# Roland_memfram.net
KiCad netlist of a schematic drawn in EAGLE
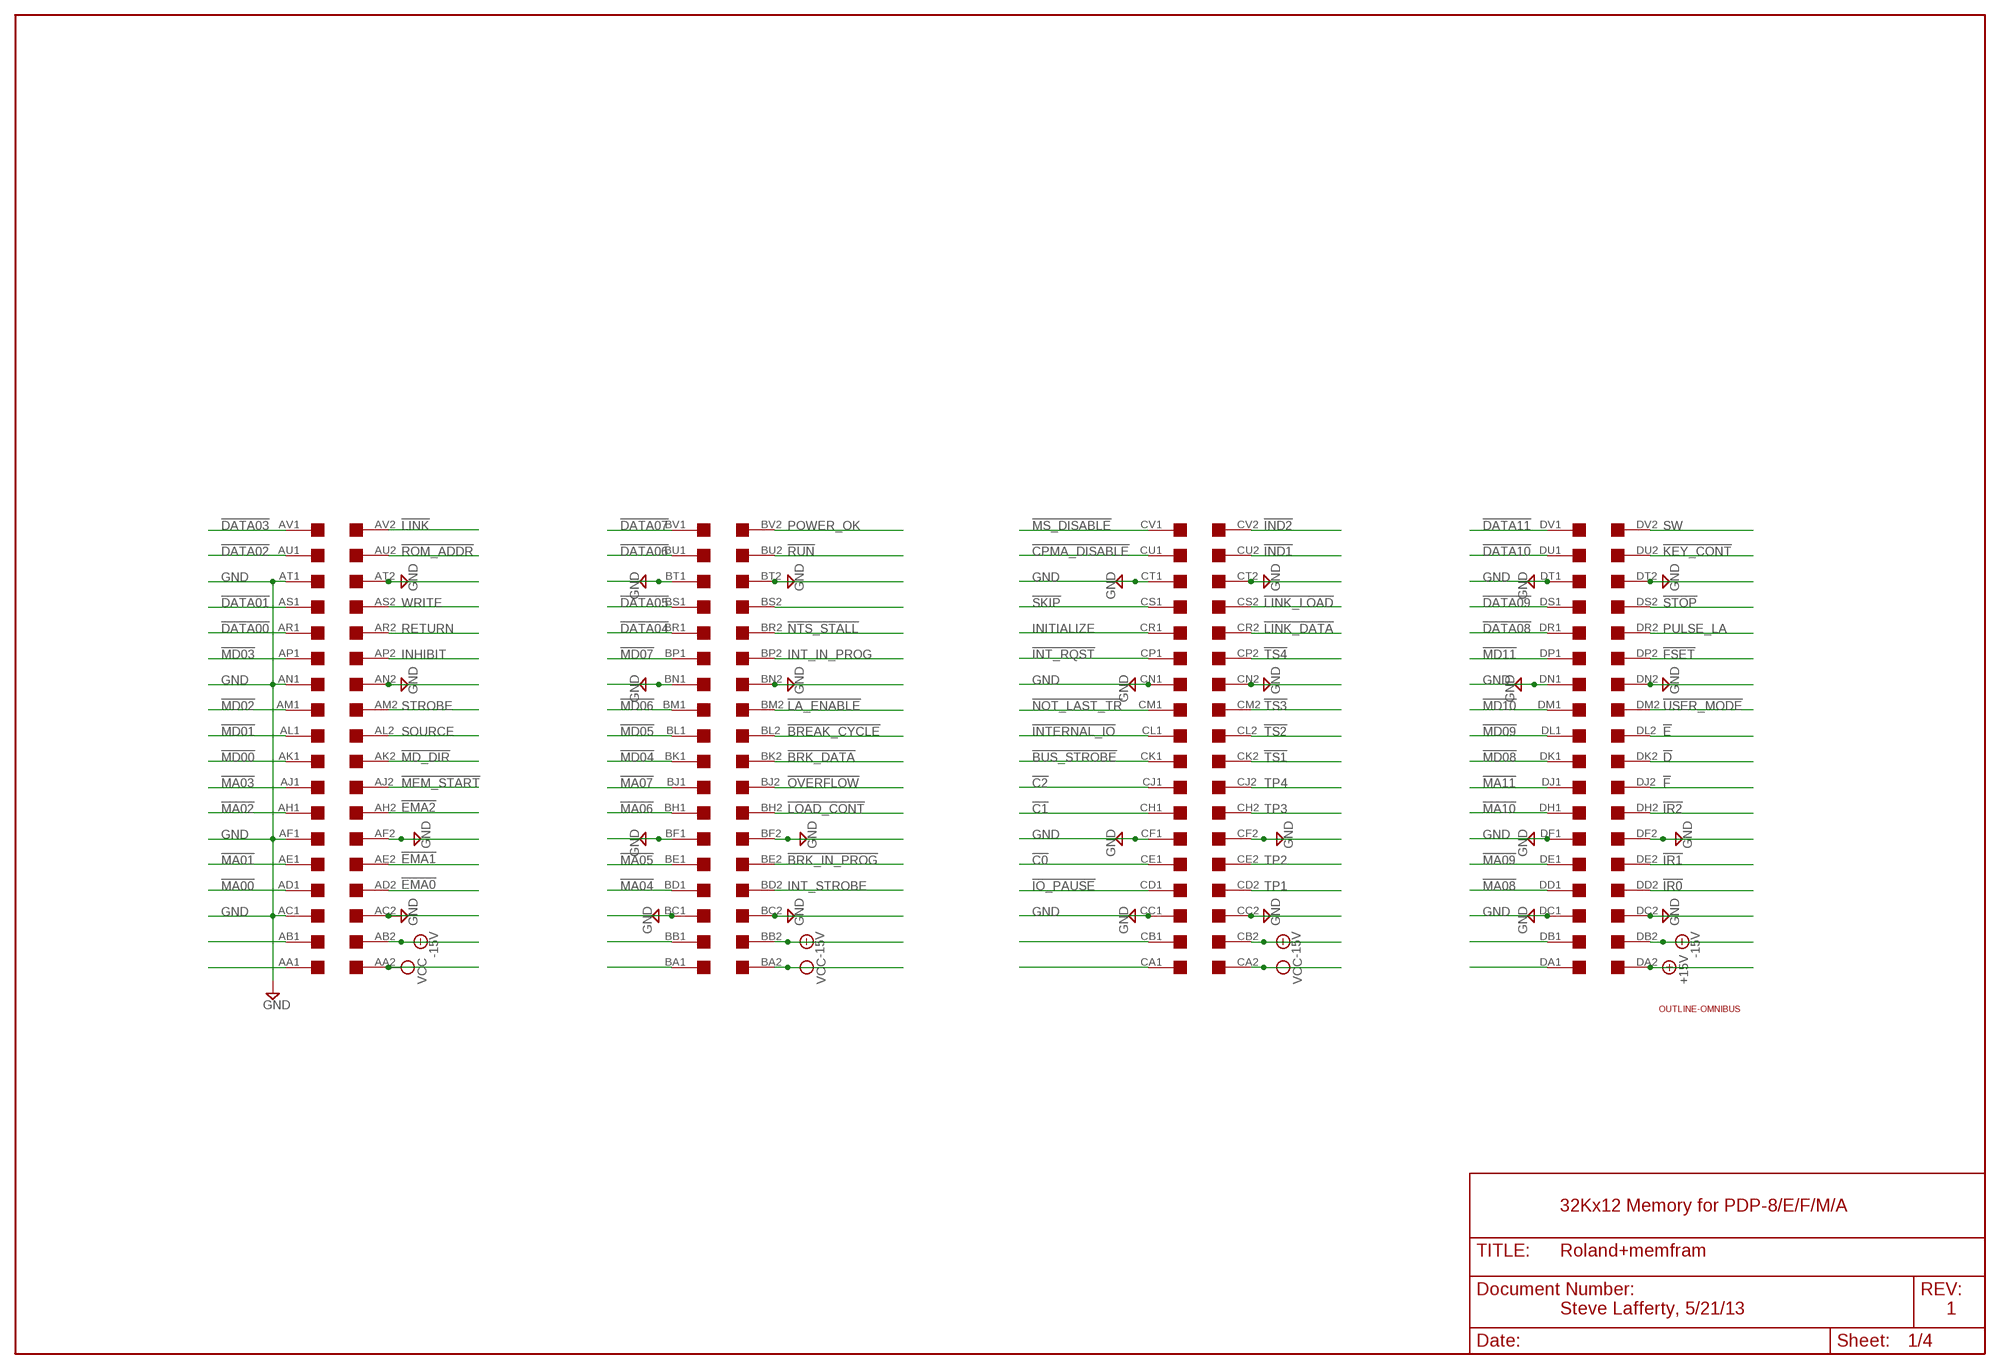
[diagram p0: schematic, sheet 1]
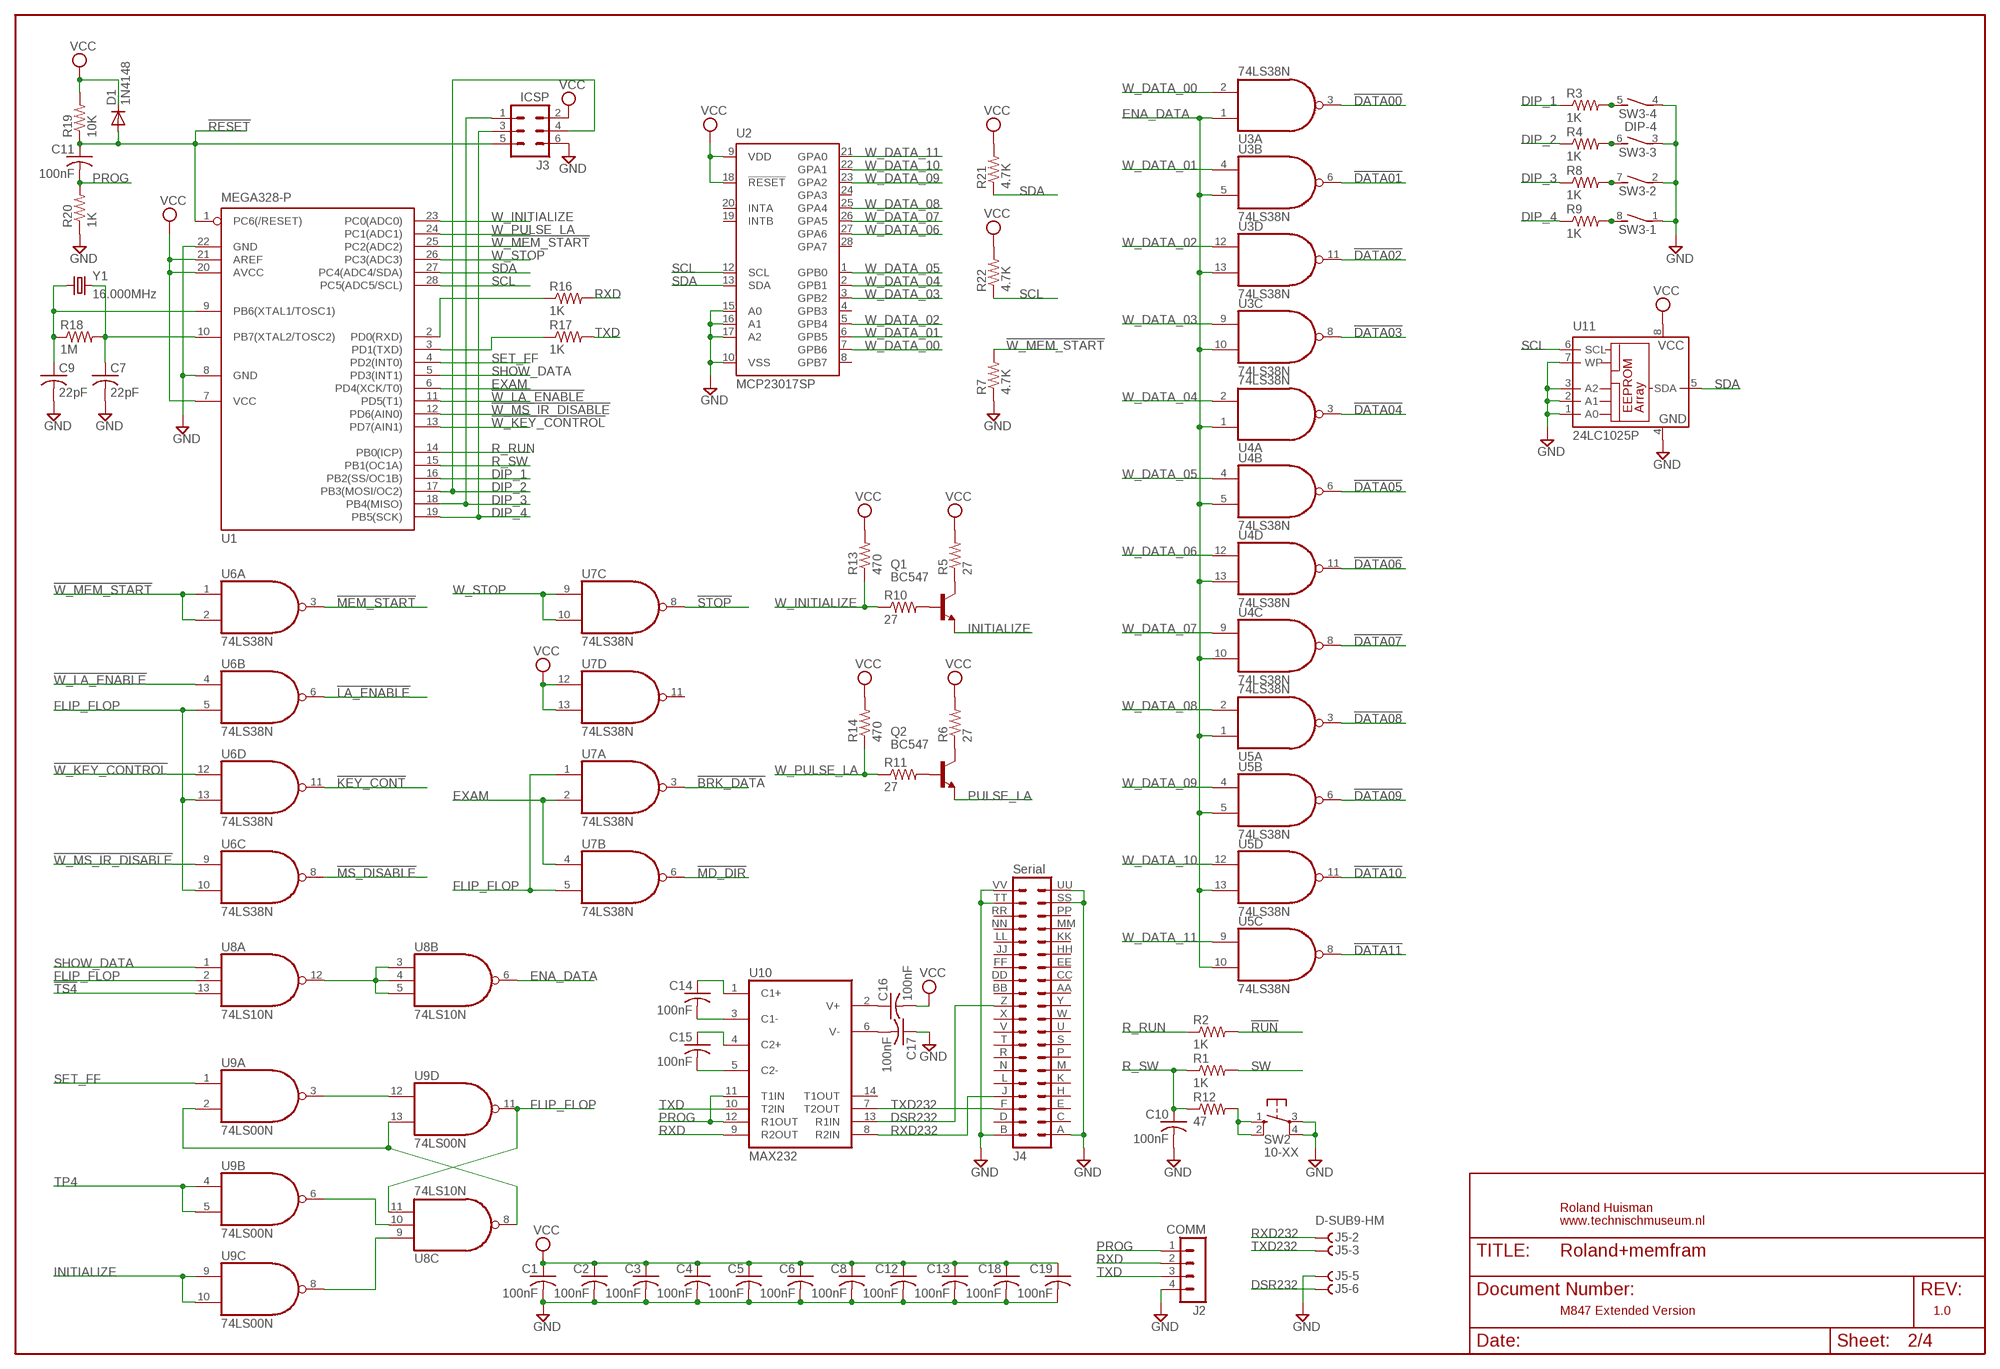
[diagram p1: schematic, sheet 2]
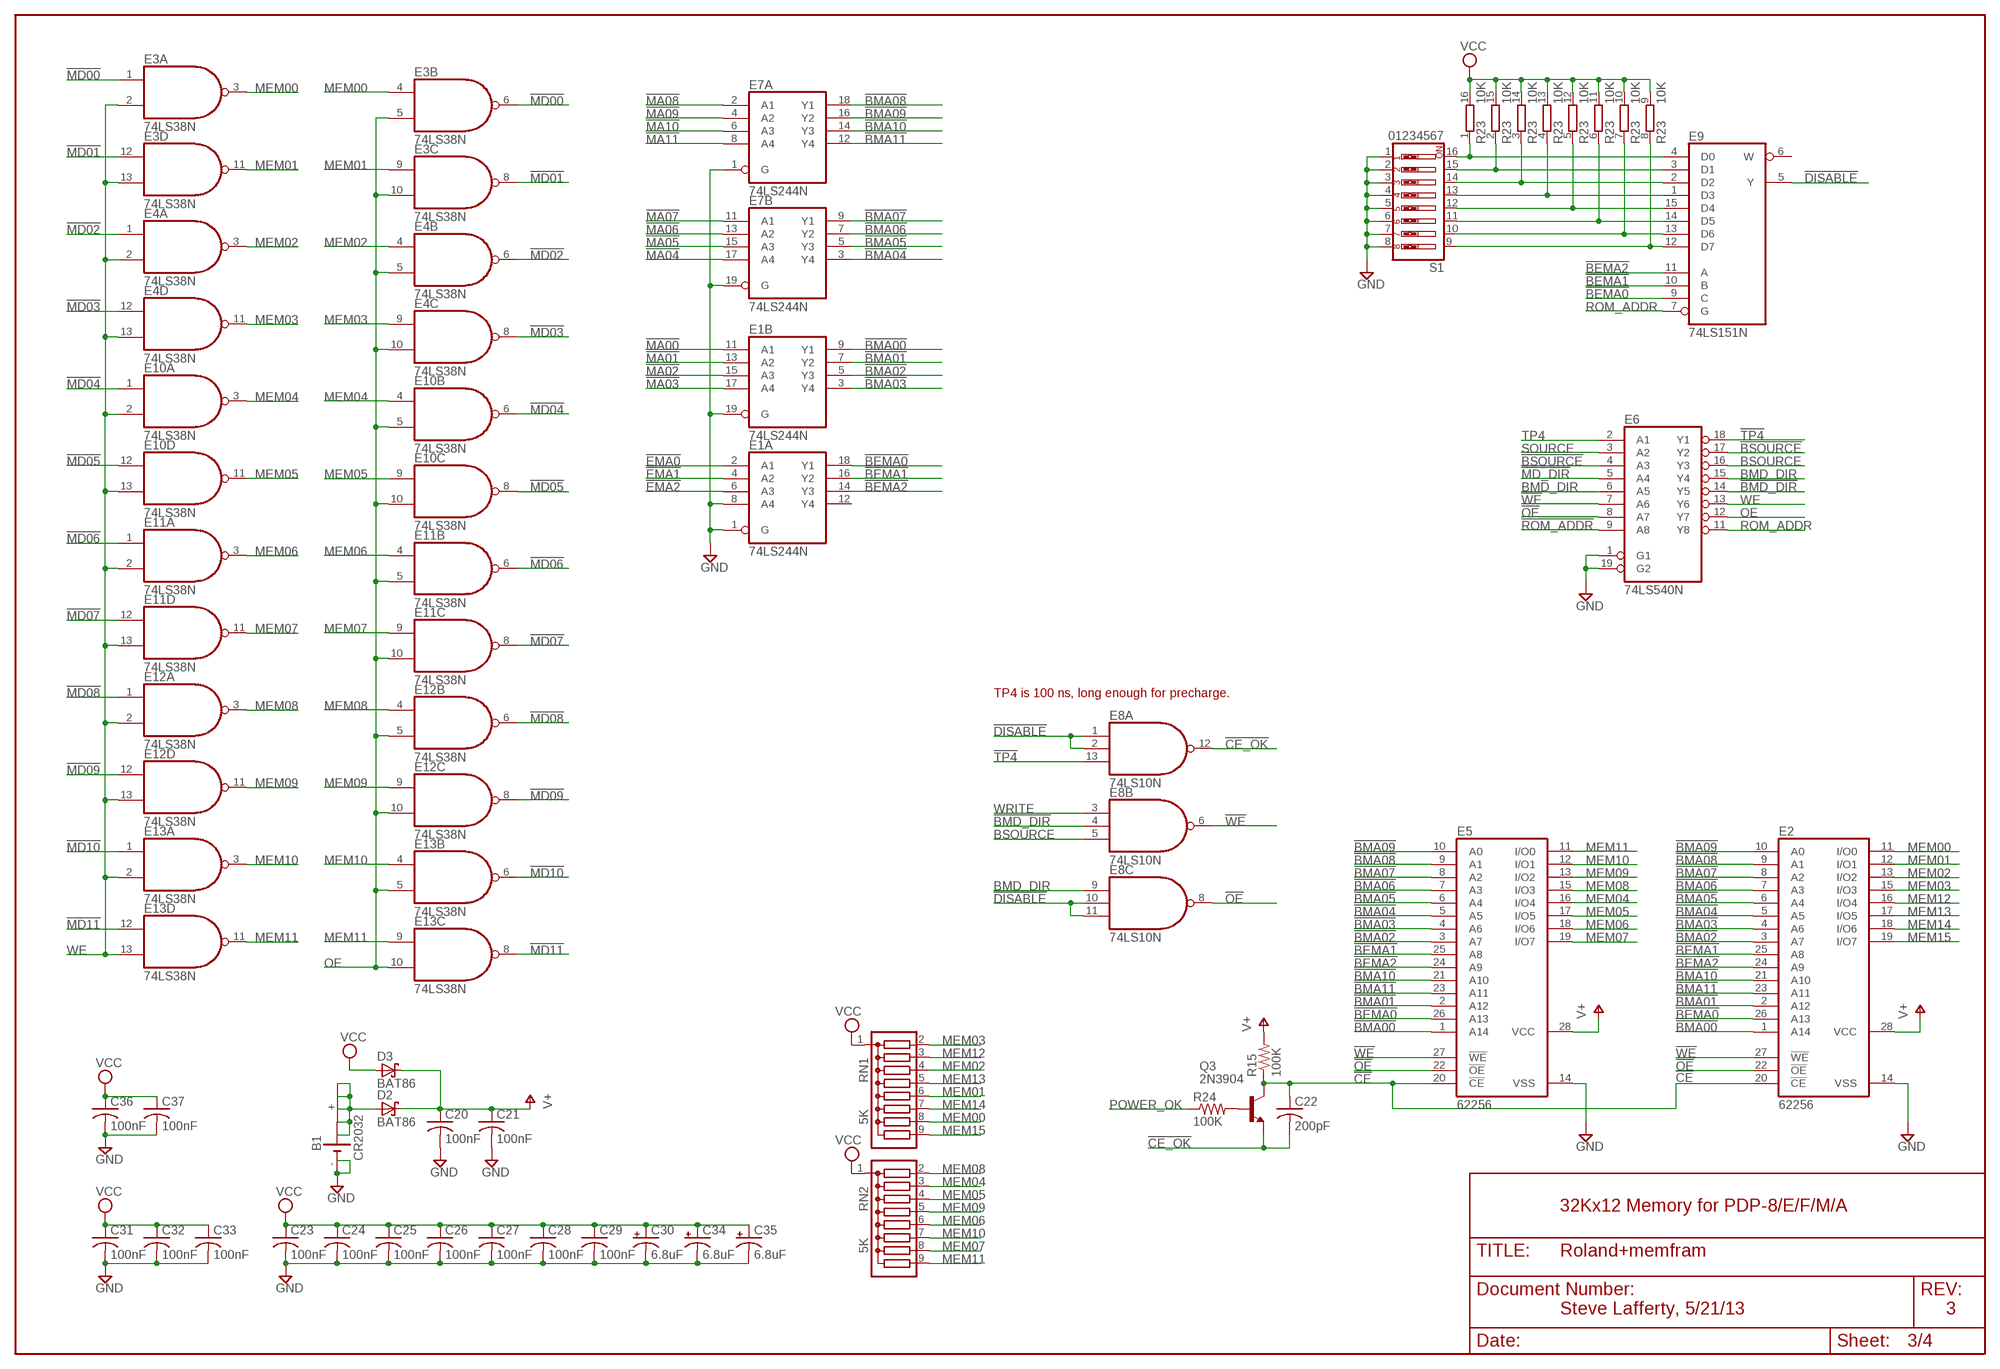
[diagram p2: schematic, sheet 3]
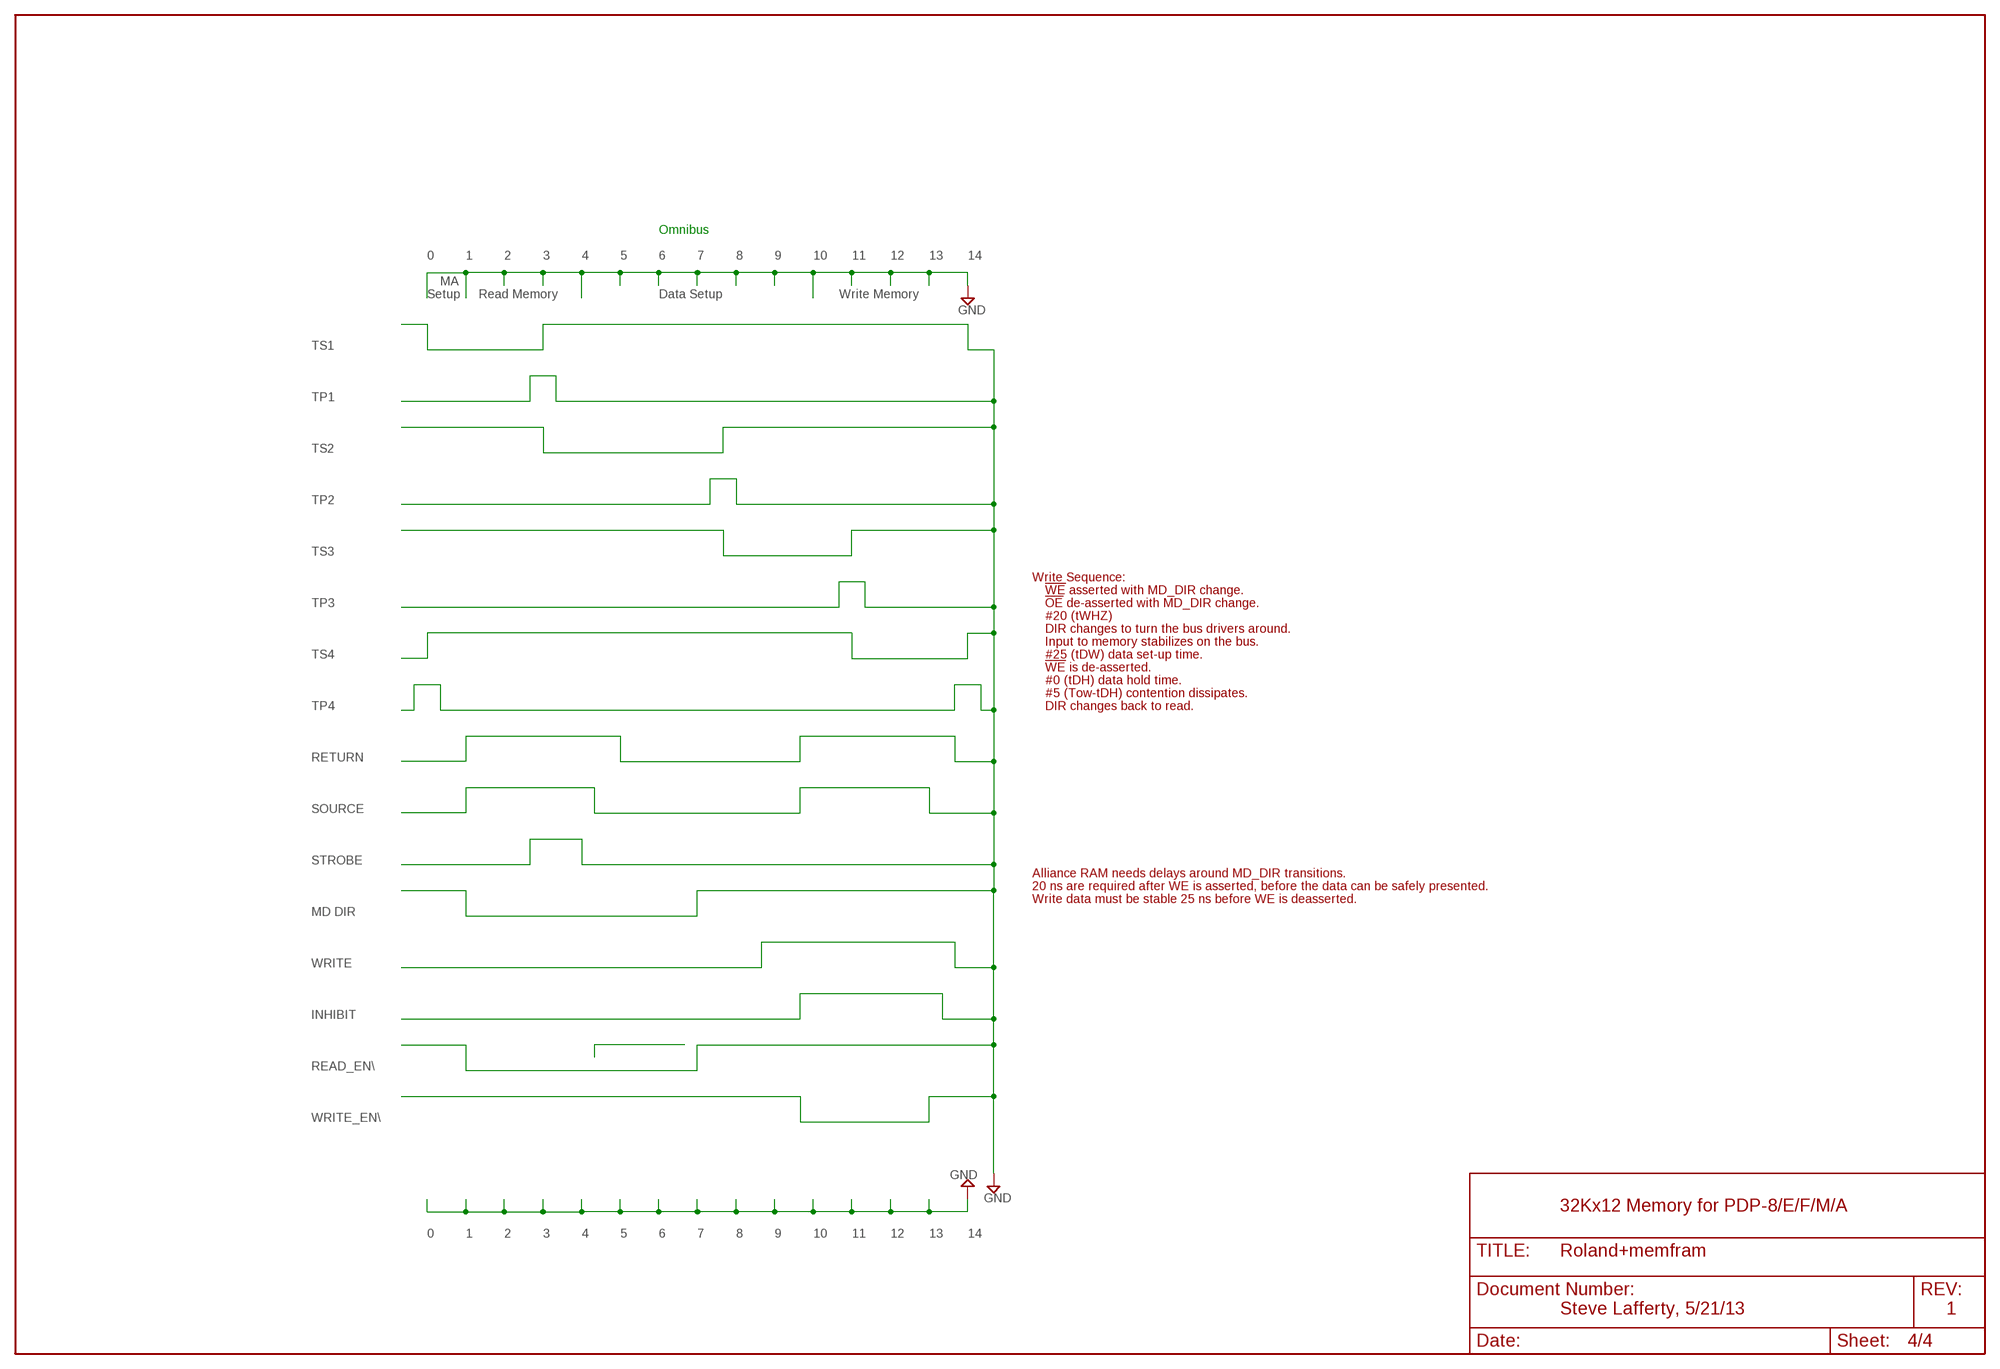
[diagram p3: schematic, sheet 4]

(export (version "E")
  (design (tool "Eeschema 10.0.6"))
  (components
    (comp (ref "J1")
      (value "EDGE")
      (footprint "eagle-import:EDGE-CON8")
      (libsource (lib "eagle-import") (part "QUAD"))
    )
    (comp (ref "U$1")
      (value "OUTLINE-OMNIBUS")
      (footprint "eagle-import:OMNIBUS")
      (libsource (lib "eagle-import") (part "OUTLINE-OMNIBUS"))
    )
    (comp (ref "B1")
      (value "CR2032")
      (footprint "eagle-import:B2430UNI")
      (libsource (lib "eagle-import") (part "B2430UNI"))
    )
    (comp (ref "C20")
      (value "100nF")
      (footprint "eagle-import:C050-025X075")
      (libsource (lib "eagle-import") (part "C-US050-025X075"))
    )
    (comp (ref "C21")
      (value "100nF")
      (footprint "eagle-import:C050-025X075")
      (libsource (lib "eagle-import") (part "C-US050-025X075"))
    )
    (comp (ref "C22")
      (value "200pF")
      (footprint "eagle-import:C050-025X075")
      (libsource (lib "eagle-import") (part "C-US050-025X075"))
    )
    (comp (ref "C23")
      (value "100nF")
      (footprint "eagle-import:C050-025X075")
      (libsource (lib "eagle-import") (part "C-US050-025X075"))
    )
    (comp (ref "C24")
      (value "100nF")
      (footprint "eagle-import:C050-025X075")
      (libsource (lib "eagle-import") (part "C-US050-025X075"))
    )
    (comp (ref "C25")
      (value "100nF")
      (footprint "eagle-import:C050-025X075")
      (libsource (lib "eagle-import") (part "C-US050-025X075"))
    )
    (comp (ref "C26")
      (value "100nF")
      (footprint "eagle-import:C050-025X075")
      (libsource (lib "eagle-import") (part "C-US050-025X075"))
    )
    (comp (ref "C27")
      (value "100nF")
      (footprint "eagle-import:C050-025X075")
      (libsource (lib "eagle-import") (part "C-US050-025X075"))
    )
    (comp (ref "C28")
      (value "100nF")
      (footprint "eagle-import:C050-025X075")
      (libsource (lib "eagle-import") (part "C-US050-025X075"))
    )
    (comp (ref "C29")
      (value "100nF")
      (footprint "eagle-import:C050-025X075")
      (libsource (lib "eagle-import") (part "C-US050-025X075"))
    )
    (comp (ref "C30")
      (value "6.8uF")
      (footprint "eagle-import:E12-8")
      (libsource (lib "eagle-import") (part "CPOL-USE20-8AXIAL"))
    )
    (comp (ref "C31")
      (value "100nF")
      (footprint "eagle-import:C050-025X075")
      (libsource (lib "eagle-import") (part "C-US050-025X075"))
    )
    (comp (ref "C32")
      (value "100nF")
      (footprint "eagle-import:C050-025X075")
      (libsource (lib "eagle-import") (part "C-US050-025X075"))
    )
    (comp (ref "C33")
      (value "100nF")
      (footprint "eagle-import:C050-025X075")
      (libsource (lib "eagle-import") (part "C-US050-025X075"))
    )
    (comp (ref "C34")
      (value "6.8uF")
      (footprint "eagle-import:E12-8")
      (libsource (lib "eagle-import") (part "CPOL-USE20-8AXIAL"))
    )
    (comp (ref "C35")
      (value "6.8uF")
      (footprint "eagle-import:E12-8")
      (libsource (lib "eagle-import") (part "CPOL-USE20-8AXIAL"))
    )
    (comp (ref "C36")
      (value "100nF")
      (footprint "eagle-import:C050-025X075")
      (libsource (lib "eagle-import") (part "C-US050-025X075"))
    )
    (comp (ref "C37")
      (value "100nF")
      (footprint "eagle-import:C050-025X075")
      (libsource (lib "eagle-import") (part "C-US050-025X075"))
    )
    (comp (ref "D2")
      (value "BAT86")
      (footprint "eagle-import:DO35-10")
      (libsource (lib "eagle-import") (part "BAT19"))
    )
    (comp (ref "D3")
      (value "BAT86")
      (footprint "eagle-import:DO35-10")
      (libsource (lib "eagle-import") (part "BAT19"))
    )
    (comp (ref "E1")
      (value "74LS244N")
      (footprint "eagle-import:DIL20")
      (libsource (lib "eagle-import") (part "74244NLS"))
    )
    (comp (ref "E2")
      (value "62256")
      (footprint "eagle-import:DIL28-6")
      (libsource (lib "eagle-import") (part "58C256P"))
    )
    (comp (ref "E3")
      (value "74LS38N")
      (footprint "eagle-import:DIL14")
      (libsource (lib "eagle-import") (part "7438NLS"))
    )
    (comp (ref "E4")
      (value "74LS38N")
      (footprint "eagle-import:DIL14")
      (libsource (lib "eagle-import") (part "7438NLS"))
    )
    (comp (ref "E5")
      (value "62256")
      (footprint "eagle-import:DIL28-6")
      (libsource (lib "eagle-import") (part "58C256P"))
    )
    (comp (ref "E6")
      (value "74LS540N")
      (footprint "eagle-import:DIL20")
      (libsource (lib "eagle-import") (part "74540NLS"))
    )
    (comp (ref "E7")
      (value "74LS244N")
      (footprint "eagle-import:DIL20")
      (libsource (lib "eagle-import") (part "74244NLS"))
    )
    (comp (ref "E8")
      (value "74LS10N")
      (footprint "eagle-import:DIL14")
      (libsource (lib "eagle-import") (part "7410NLS"))
    )
    (comp (ref "E9")
      (value "74LS151N")
      (footprint "eagle-import:DIL16")
      (libsource (lib "eagle-import") (part "74151NLS"))
    )
    (comp (ref "E10")
      (value "74LS38N")
      (footprint "eagle-import:DIL14")
      (libsource (lib "eagle-import") (part "7438NLS"))
    )
    (comp (ref "E11")
      (value "74LS38N")
      (footprint "eagle-import:DIL14")
      (libsource (lib "eagle-import") (part "7438NLS"))
    )
    (comp (ref "E12")
      (value "74LS38N")
      (footprint "eagle-import:DIL14")
      (libsource (lib "eagle-import") (part "7438NLS"))
    )
    (comp (ref "E13")
      (value "74LS38N")
      (footprint "eagle-import:DIL14")
      (libsource (lib "eagle-import") (part "7438NLS"))
    )
    (comp (ref "Q3")
      (value "2N3904")
      (footprint "eagle-import:TO92")
      (libsource (lib "eagle-import") (part "2N3904"))
    )
    (comp (ref "R15")
      (value "100K")
      (footprint "eagle-import:0207_10")
      (libsource (lib "eagle-import") (part "R-US_0207/10"))
    )
    (comp (ref "R23")
      (value "10K")
      (footprint "eagle-import:DIL16")
      (libsource (lib "eagle-import") (part "8R-P"))
    )
    (comp (ref "R24")
      (value "100K")
      (footprint "eagle-import:0207_10")
      (libsource (lib "eagle-import") (part "R-US_0207/10"))
    )
    (comp (ref "RN1")
      (value "5K")
      (footprint "eagle-import:SIL9")
      (libsource (lib "eagle-import") (part "G08R"))
    )
    (comp (ref "RN2")
      (value "5K")
      (footprint "eagle-import:SIL9")
      (libsource (lib "eagle-import") (part "G08R"))
    )
    (comp (ref "S1")
      (value "01234567")
      (footprint "eagle-import:EDG-08")
      (libsource (lib "eagle-import") (part "SW_DIP-8"))
    )
    (comp (ref "C1")
      (value "100nF")
      (footprint "eagle-import:C050-025X075")
      (libsource (lib "eagle-import") (part "C-US050-025X075"))
    )
    (comp (ref "C2")
      (value "100nF")
      (footprint "eagle-import:C050-025X075")
      (libsource (lib "eagle-import") (part "C-US050-025X075"))
    )
    (comp (ref "C3")
      (value "100nF")
      (footprint "eagle-import:C050-025X075")
      (libsource (lib "eagle-import") (part "C-US050-025X075"))
    )
    (comp (ref "C4")
      (value "100nF")
      (footprint "eagle-import:C050-025X075")
      (libsource (lib "eagle-import") (part "C-US050-025X075"))
    )
    (comp (ref "C5")
      (value "100nF")
      (footprint "eagle-import:C050-025X075")
      (libsource (lib "eagle-import") (part "C-US050-025X075"))
    )
    (comp (ref "C6")
      (value "100nF")
      (footprint "eagle-import:C050-025X075")
      (libsource (lib "eagle-import") (part "C-US050-025X075"))
    )
    (comp (ref "C7")
      (value "22pF")
      (footprint "eagle-import:C050-025X075")
      (libsource (lib "eagle-import") (part "C-US050-025X075"))
    )
    (comp (ref "C8")
      (value "100nF")
      (footprint "eagle-import:C050-025X075")
      (libsource (lib "eagle-import") (part "C-US050-025X075"))
    )
    (comp (ref "C9")
      (value "22pF")
      (footprint "eagle-import:C050-025X075")
      (libsource (lib "eagle-import") (part "C-US050-025X075"))
    )
    (comp (ref "C10")
      (value "100nF")
      (footprint "eagle-import:C050-025X075")
      (libsource (lib "eagle-import") (part "C-US050-025X075"))
    )
    (comp (ref "C11")
      (value "100nF")
      (footprint "eagle-import:C050-025X075")
      (libsource (lib "eagle-import") (part "C-US050-025X075"))
    )
    (comp (ref "C12")
      (value "100nF")
      (footprint "eagle-import:C050-025X075")
      (libsource (lib "eagle-import") (part "C-US050-025X075"))
    )
    (comp (ref "C13")
      (value "100nF")
      (footprint "eagle-import:C050-025X075")
      (libsource (lib "eagle-import") (part "C-US050-025X075"))
    )
    (comp (ref "C14")
      (value "100nF")
      (footprint "eagle-import:C050-025X075")
      (libsource (lib "eagle-import") (part "C-US050-025X075"))
    )
    (comp (ref "C15")
      (value "100nF")
      (footprint "eagle-import:C050-025X075")
      (libsource (lib "eagle-import") (part "C-US050-025X075"))
    )
    (comp (ref "C16")
      (value "100nF")
      (footprint "eagle-import:C050-025X075")
      (libsource (lib "eagle-import") (part "C-US050-025X075"))
    )
    (comp (ref "C17")
      (value "100nF")
      (footprint "eagle-import:C050-025X075")
      (libsource (lib "eagle-import") (part "C-US050-025X075"))
    )
    (comp (ref "C18")
      (value "100nF")
      (footprint "eagle-import:C050-025X075")
      (libsource (lib "eagle-import") (part "C-US050-025X075"))
    )
    (comp (ref "C19")
      (value "100nF")
      (footprint "eagle-import:C050-025X075")
      (libsource (lib "eagle-import") (part "C-US050-025X075"))
    )
    (comp (ref "D1")
      (value "1N4148")
      (footprint "eagle-import:DO35-10")
      (libsource (lib "eagle-import") (part "1N4148DO35-10"))
    )
    (comp (ref "J2")
      (value "COMM")
      (footprint "eagle-import:MA04-1")
      (libsource (lib "eagle-import") (part "MA04-1"))
    )
    (comp (ref "J3")
      (value "ICSP")
      (footprint "eagle-import:MA03-2")
      (libsource (lib "eagle-import") (part "MA03-2"))
    )
    (comp (ref "J4")
      (value "Serial")
      (footprint "eagle-import:DEC40PINH")
      (libsource (lib "eagle-import") (part "DEC40PINH"))
    )
    (comp (ref "J5")
      (value "D-SUB9-HM")
      (footprint "eagle-import:H5M09RA")
      (libsource (lib "eagle-import") (part "D-SUB9-H5M09RA"))
    )
    (comp (ref "Q1")
      (value "BC547")
      (footprint "eagle-import:TO5")
      (libsource (lib "eagle-import") (part "-NPN-TO5"))
    )
    (comp (ref "Q2")
      (value "BC547")
      (footprint "eagle-import:TO5")
      (libsource (lib "eagle-import") (part "-NPN-TO5"))
    )
    (comp (ref "R1")
      (value "1K")
      (footprint "eagle-import:0207_10")
      (libsource (lib "eagle-import") (part "R-US_0207/10"))
    )
    (comp (ref "R2")
      (value "1K")
      (footprint "eagle-import:0207_10")
      (libsource (lib "eagle-import") (part "R-US_0207/10"))
    )
    (comp (ref "R3")
      (value "1K")
      (footprint "eagle-import:0207_10")
      (libsource (lib "eagle-import") (part "R-US_0207/10"))
    )
    (comp (ref "R4")
      (value "1K")
      (footprint "eagle-import:0207_10")
      (libsource (lib "eagle-import") (part "R-US_0207/10"))
    )
    (comp (ref "R5")
      (value "27")
      (footprint "eagle-import:0207_10")
      (libsource (lib "eagle-import") (part "R-US_0207/10"))
    )
    (comp (ref "R6")
      (value "27")
      (footprint "eagle-import:0207_10")
      (libsource (lib "eagle-import") (part "R-US_0207/10"))
    )
    (comp (ref "R7")
      (value "4.7K")
      (footprint "eagle-import:0207_10")
      (libsource (lib "eagle-import") (part "R-US_0207/10"))
    )
    (comp (ref "R8")
      (value "1K")
      (footprint "eagle-import:0207_10")
      (libsource (lib "eagle-import") (part "R-US_0207/10"))
    )
    (comp (ref "R9")
      (value "1K")
      (footprint "eagle-import:0207_10")
      (libsource (lib "eagle-import") (part "R-US_0207/10"))
    )
    (comp (ref "R10")
      (value "27")
      (footprint "eagle-import:0207_10")
      (libsource (lib "eagle-import") (part "R-US_0207/10"))
    )
    (comp (ref "R11")
      (value "27")
      (footprint "eagle-import:0207_10")
      (libsource (lib "eagle-import") (part "R-US_0207/10"))
    )
    (comp (ref "R12")
      (value "47")
      (footprint "eagle-import:0207_10")
      (libsource (lib "eagle-import") (part "R-US_0207/10"))
    )
    (comp (ref "R13")
      (value "470")
      (footprint "eagle-import:0207_10")
      (libsource (lib "eagle-import") (part "R-US_0207/10"))
    )
    (comp (ref "R14")
      (value "470")
      (footprint "eagle-import:0207_10")
      (libsource (lib "eagle-import") (part "R-US_0207/10"))
    )
    (comp (ref "R16")
      (value "1K")
      (footprint "eagle-import:0207_10")
      (libsource (lib "eagle-import") (part "R-US_0207/10"))
    )
    (comp (ref "R17")
      (value "1K")
      (footprint "eagle-import:0207_10")
      (libsource (lib "eagle-import") (part "R-US_0207/10"))
    )
    (comp (ref "R18")
      (value "1M")
      (footprint "eagle-import:0207_10")
      (libsource (lib "eagle-import") (part "R-US_0207/10"))
    )
    (comp (ref "R19")
      (value "10K")
      (footprint "eagle-import:0207_10")
      (libsource (lib "eagle-import") (part "R-US_0207/10"))
    )
    (comp (ref "R20")
      (value "1K")
      (footprint "eagle-import:0207_10")
      (libsource (lib "eagle-import") (part "R-US_0207/10"))
    )
    (comp (ref "R21")
      (value "4.7K")
      (footprint "eagle-import:0207_10")
      (libsource (lib "eagle-import") (part "R-US_0207/10"))
    )
    (comp (ref "R22")
      (value "4.7K")
      (footprint "eagle-import:0207_10")
      (libsource (lib "eagle-import") (part "R-US_0207/10"))
    )
    (comp (ref "SW2")
      (value "10-XX")
      (footprint "eagle-import:B3F-10XX")
      (fields (field (name "MPN") "B3F-1000"))
      (libsource (lib "eagle-import") (part "10-XX"))
    )
    (comp (ref "SW3")
      (value "DIP-4")
      (footprint "eagle-import:DIP04S")
      (libsource (lib "eagle-import") (part "DIP04S"))
    )
    (comp (ref "U1")
      (value "MEGA328-P")
      (footprint "eagle-import:DIL28-3")
      (libsource (lib "eagle-import") (part "MEGA8-P"))
    )
    (comp (ref "U2")
      (value "MCP23017SP")
      (footprint "eagle-import:DIL28-3")
      (fields (field (name "MF") "MICROCHIP") (field (name "MPN") "MCP23017-E/SP"))
      (libsource (lib "eagle-import") (part "MCP23017SP"))
    )
    (comp (ref "U3")
      (value "74LS38N")
      (footprint "eagle-import:DIL14")
      (libsource (lib "eagle-import") (part "7438NLS"))
    )
    (comp (ref "U4")
      (value "74LS38N")
      (footprint "eagle-import:DIL14")
      (libsource (lib "eagle-import") (part "7438NLS"))
    )
    (comp (ref "U5")
      (value "74LS38N")
      (footprint "eagle-import:DIL14")
      (libsource (lib "eagle-import") (part "7438NLS"))
    )
    (comp (ref "U6")
      (value "74LS38N")
      (footprint "eagle-import:DIL14")
      (libsource (lib "eagle-import") (part "7438NLS"))
    )
    (comp (ref "U7")
      (value "74LS38N")
      (footprint "eagle-import:DIL14")
      (libsource (lib "eagle-import") (part "7438NLS"))
    )
    (comp (ref "U8")
      (value "74LS10N")
      (footprint "eagle-import:DIL14")
      (libsource (lib "eagle-import") (part "7410NLS"))
    )
    (comp (ref "U9")
      (value "74LS00N")
      (footprint "eagle-import:DIL14")
      (libsource (lib "eagle-import") (part "7400NLS"))
    )
    (comp (ref "U10")
      (value "MAX232")
      (footprint "eagle-import:DIL16")
      (fields (field (name "MF") "MAXIM") (field (name "MPN") "MAX232ACPE+"))
      (libsource (lib "eagle-import") (part "MAX232"))
    )
    (comp (ref "U11")
      (value "24LC1025P")
      (footprint "eagle-import:DIL8")
      (fields (field (name "MF") "MICROCHIP") (field (name "MPN") "24LC025-I/P"))
      (libsource (lib "eagle-import") (part "24PLC025"))
    )
    (comp (ref "Y1")
      (value "16.000MHz")
      (footprint "eagle-import:HC49U-H")
      (libsource (lib "eagle-import") (part "CRYSTALHC49U-H"))
    )
  )
  (nets
    (net (code "1") (name "+15V") (class "Default")
      (node (ref "J1") (pin "DA2") (pinfunction "1_DA2") (pintype "bidirectional"))
    )
    (net (code "2") (name "-15V") (class "Default")
      (node (ref "J1") (pin "AB2") (pinfunction "1_AB2") (pintype "bidirectional"))
      (node (ref "J1") (pin "BB2") (pinfunction "1_BB2") (pintype "bidirectional"))
      (node (ref "J1") (pin "CB2") (pinfunction "1_CB2") (pintype "bidirectional"))
      (node (ref "J1") (pin "DB2") (pinfunction "1_DB2") (pintype "bidirectional"))
    )
    (net (code "3") (name "BMD_DIR") (class "Default")
      (node (ref "E6") (pin "15") (pinfunction "Y4_15") (pintype "tri_state"))
      (node (ref "E6") (pin "6") (pinfunction "A5_6") (pintype "input"))
      (node (ref "E8") (pin "9") (pinfunction "I0_9") (pintype "input"))
    )
    (net (code "4") (name "BSOURCE") (class "Default")
      (node (ref "E6") (pin "16") (pinfunction "Y3_16") (pintype "tri_state"))
      (node (ref "E8") (pin "5") (pinfunction "I2_5") (pintype "input"))
    )
    (net (code "5") (name "DIP_1") (class "Default")
      (node (ref "R3") (pin "1") (pinfunction "1_1") (pintype "passive"))
      (node (ref "U1") (pin "16") (pinfunction "PB2(SS/OC1B)_16") (pintype "bidirectional"))
    )
    (net (code "6") (name "DIP_2") (class "Default")
      (node (ref "J3") (pin "4") (pinfunction "4_4") (pintype "passive"))
      (node (ref "R4") (pin "1") (pinfunction "1_1") (pintype "passive"))
      (node (ref "U1") (pin "17") (pinfunction "PB3(MOSI/OC2)_17") (pintype "bidirectional"))
    )
    (net (code "7") (name "DIP_3") (class "Default")
      (node (ref "J3") (pin "1") (pinfunction "1_1") (pintype "passive"))
      (node (ref "R8") (pin "1") (pinfunction "1_1") (pintype "passive"))
      (node (ref "U1") (pin "18") (pinfunction "PB4(MISO)_18") (pintype "bidirectional"))
    )
    (net (code "8") (name "DIP_4") (class "Default")
      (node (ref "J3") (pin "3") (pinfunction "3_3") (pintype "passive"))
      (node (ref "R9") (pin "1") (pinfunction "1_1") (pintype "passive"))
      (node (ref "U1") (pin "19") (pinfunction "PB5(SCK)_19") (pintype "bidirectional"))
    )
    (net (code "9") (name "DSR232") (class "Default")
      (node (ref "J4") (pin "Z") (pinfunction "22_Z") (pintype "bidirectional"))
      (node (ref "J5") (pin "6") (pinfunction "F_6") (pintype "passive"))
      (node (ref "U10") (pin "13") (pinfunction "R1IN_13") (pintype "input"))
    )
    (net (code "10") (name "ENA_DATA") (class "Default")
      (node (ref "U3") (pin "1") (pinfunction "I0_1") (pintype "input"))
      (node (ref "U3") (pin "10") (pinfunction "I1_10") (pintype "input"))
      (node (ref "U3") (pin "13") (pinfunction "I1_13") (pintype "input"))
      (node (ref "U3") (pin "5") (pinfunction "I1_5") (pintype "input"))
      (node (ref "U4") (pin "1") (pinfunction "I0_1") (pintype "input"))
      (node (ref "U4") (pin "10") (pinfunction "I1_10") (pintype "input"))
      (node (ref "U4") (pin "13") (pinfunction "I1_13") (pintype "input"))
      (node (ref "U4") (pin "5") (pinfunction "I1_5") (pintype "input"))
      (node (ref "U5") (pin "1") (pinfunction "I0_1") (pintype "input"))
      (node (ref "U5") (pin "10") (pinfunction "I1_10") (pintype "input"))
      (node (ref "U5") (pin "13") (pinfunction "I1_13") (pintype "input"))
      (node (ref "U5") (pin "5") (pinfunction "I1_5") (pintype "input"))
      (node (ref "U8") (pin "6") (pinfunction "O_6") (pintype "output"))
    )
    (net (code "11") (name "EXAM") (class "Default")
      (node (ref "U1") (pin "6") (pinfunction "PD4(XCK/T0)_6") (pintype "bidirectional"))
      (node (ref "U7") (pin "2") (pinfunction "I1_2") (pintype "input"))
      (node (ref "U7") (pin "4") (pinfunction "I0_4") (pintype "input"))
    )
    (net (code "12") (name "FLIP_FLOP") (class "Default")
      (node (ref "U6") (pin "10") (pinfunction "I1_10") (pintype "input"))
      (node (ref "U6") (pin "13") (pinfunction "I1_13") (pintype "input"))
      (node (ref "U6") (pin "5") (pinfunction "I1_5") (pintype "input"))
      (node (ref "U7") (pin "1") (pinfunction "I0_1") (pintype "input"))
      (node (ref "U7") (pin "5") (pinfunction "I1_5") (pintype "input"))
      (node (ref "U8") (pin "11") (pinfunction "I2_11") (pintype "input"))
      (node (ref "U8") (pin "2") (pinfunction "I1_2") (pintype "input"))
      (node (ref "U9") (pin "11") (pinfunction "O_11") (pintype "output"))
    )
    (net (code "13") (name "GND") (class "Default")
      (node (ref "B1") (pin "-") (pinfunction "-_-") (pintype "passive"))
      (node (ref "B1") (pin "-@1") (pinfunction "-_-@1") (pintype "passive"))
      (node (ref "C1") (pin "2") (pinfunction "2_2") (pintype "passive"))
      (node (ref "C10") (pin "2") (pinfunction "2_2") (pintype "passive"))
      (node (ref "C12") (pin "2") (pinfunction "2_2") (pintype "passive"))
      (node (ref "C13") (pin "2") (pinfunction "2_2") (pintype "passive"))
      (node (ref "C17") (pin "1") (pinfunction "1_1") (pintype "passive"))
      (node (ref "C18") (pin "2") (pinfunction "2_2") (pintype "passive"))
      (node (ref "C19") (pin "2") (pinfunction "2_2") (pintype "passive"))
      (node (ref "C2") (pin "2") (pinfunction "2_2") (pintype "passive"))
      (node (ref "C20") (pin "2") (pinfunction "2_2") (pintype "passive"))
      (node (ref "C21") (pin "2") (pinfunction "2_2") (pintype "passive"))
      (node (ref "C23") (pin "2") (pinfunction "2_2") (pintype "passive"))
      (node (ref "C24") (pin "2") (pinfunction "2_2") (pintype "passive"))
      (node (ref "C25") (pin "2") (pinfunction "2_2") (pintype "passive"))
      (node (ref "C26") (pin "2") (pinfunction "2_2") (pintype "passive"))
      (node (ref "C27") (pin "2") (pinfunction "2_2") (pintype "passive"))
      (node (ref "C28") (pin "2") (pinfunction "2_2") (pintype "passive"))
      (node (ref "C29") (pin "2") (pinfunction "2_2") (pintype "passive"))
      (node (ref "C3") (pin "2") (pinfunction "2_2") (pintype "passive"))
      (node (ref "C30") (pin "-") (pinfunction "-_-") (pintype "passive"))
      (node (ref "C31") (pin "2") (pinfunction "2_2") (pintype "passive"))
      (node (ref "C32") (pin "2") (pinfunction "2_2") (pintype "passive"))
      (node (ref "C33") (pin "2") (pinfunction "2_2") (pintype "passive"))
      (node (ref "C34") (pin "-") (pinfunction "-_-") (pintype "passive"))
      (node (ref "C35") (pin "-") (pinfunction "-_-") (pintype "passive"))
      (node (ref "C36") (pin "2") (pinfunction "2_2") (pintype "passive"))
      (node (ref "C37") (pin "2") (pinfunction "2_2") (pintype "passive"))
      (node (ref "C4") (pin "2") (pinfunction "2_2") (pintype "passive"))
      (node (ref "C5") (pin "2") (pinfunction "2_2") (pintype "passive"))
      (node (ref "C6") (pin "2") (pinfunction "2_2") (pintype "passive"))
      (node (ref "C7") (pin "2") (pinfunction "2_2") (pintype "passive"))
      (node (ref "C8") (pin "2") (pinfunction "2_2") (pintype "passive"))
      (node (ref "C9") (pin "2") (pinfunction "2_2") (pintype "passive"))
      (node (ref "E1") (pin "1") (pinfunction "G_1") (pintype "input"))
      (node (ref "E1") (pin "19") (pinfunction "G_19") (pintype "input"))
      (node (ref "E1") (pin "8") (pinfunction "A4_8") (pintype "input"))
      (node (ref "E2") (pin "14") (pinfunction "VSS_14") (pintype "power_in"))
      (node (ref "E5") (pin "14") (pinfunction "VSS_14") (pintype "power_in"))
      (node (ref "E6") (pin "1") (pinfunction "G1_1") (pintype "input"))
      (node (ref "E6") (pin "19") (pinfunction "G2_19") (pintype "input"))
      (node (ref "E7") (pin "1") (pinfunction "G_1") (pintype "input"))
      (node (ref "E7") (pin "19") (pinfunction "G_19") (pintype "input"))
      (node (ref "J1") (pin "AC1") (pinfunction "1_AC1") (pintype "bidirectional"))
      (node (ref "J1") (pin "AC2") (pinfunction "1_AC2") (pintype "bidirectional"))
      (node (ref "J1") (pin "AF1") (pinfunction "1_AF1") (pintype "bidirectional"))
      (node (ref "J1") (pin "AF2") (pinfunction "1_AF2") (pintype "bidirectional"))
      (node (ref "J1") (pin "AN1") (pinfunction "1_AN1") (pintype "bidirectional"))
      (node (ref "J1") (pin "AN2") (pinfunction "1_AN2") (pintype "bidirectional"))
      (node (ref "J1") (pin "AT1") (pinfunction "1_AT1") (pintype "bidirectional"))
      (node (ref "J1") (pin "AT2") (pinfunction "1_AT2") (pintype "bidirectional"))
      (node (ref "J1") (pin "BC1") (pinfunction "1_BC1") (pintype "bidirectional"))
      (node (ref "J1") (pin "BC2") (pinfunction "1_BC2") (pintype "bidirectional"))
      (node (ref "J1") (pin "BF1") (pinfunction "1_BF1") (pintype "bidirectional"))
      (node (ref "J1") (pin "BF2") (pinfunction "1_BF2") (pintype "bidirectional"))
      (node (ref "J1") (pin "BN1") (pinfunction "1_BN1") (pintype "bidirectional"))
      (node (ref "J1") (pin "BN2") (pinfunction "1_BN2") (pintype "bidirectional"))
      (node (ref "J1") (pin "BT1") (pinfunction "1_BT1") (pintype "bidirectional"))
      (node (ref "J1") (pin "BT2") (pinfunction "1_BT2") (pintype "bidirectional"))
      (node (ref "J1") (pin "CC1") (pinfunction "1_CC1") (pintype "bidirectional"))
      (node (ref "J1") (pin "CC2") (pinfunction "1_CC2") (pintype "bidirectional"))
      (node (ref "J1") (pin "CF1") (pinfunction "1_CF1") (pintype "bidirectional"))
      (node (ref "J1") (pin "CF2") (pinfunction "1_CF2") (pintype "bidirectional"))
      (node (ref "J1") (pin "CN1") (pinfunction "1_CN1") (pintype "bidirectional"))
      (node (ref "J1") (pin "CN2") (pinfunction "1_CN2") (pintype "bidirectional"))
      (node (ref "J1") (pin "CT1") (pinfunction "1_CT1") (pintype "bidirectional"))
      (node (ref "J1") (pin "CT2") (pinfunction "1_CT2") (pintype "bidirectional"))
      (node (ref "J1") (pin "DC1") (pinfunction "1_DC1") (pintype "bidirectional"))
      (node (ref "J1") (pin "DC2") (pinfunction "1_DC2") (pintype "bidirectional"))
      (node (ref "J1") (pin "DF1") (pinfunction "1_DF1") (pintype "bidirectional"))
      (node (ref "J1") (pin "DF2") (pinfunction "1_DF2") (pintype "bidirectional"))
      (node (ref "J1") (pin "DN1") (pinfunction "1_DN1") (pintype "bidirectional"))
      (node (ref "J1") (pin "DN2") (pinfunction "1_DN2") (pintype "bidirectional"))
      (node (ref "J1") (pin "DT1") (pinfunction "1_DT1") (pintype "bidirectional"))
      (node (ref "J1") (pin "DT2") (pinfunction "1_DT2") (pintype "bidirectional"))
      (node (ref "J2") (pin "4") (pinfunction "4_4") (pintype "passive"))
      (node (ref "J3") (pin "6") (pinfunction "6_6") (pintype "passive"))
      (node (ref "J4") (pin "A") (pinfunction "1_A") (pintype "bidirectional"))
      (node (ref "J4") (pin "B") (pinfunction "2_B") (pintype "bidirectional"))
      (node (ref "J4") (pin "SS") (pinfunction "37_SS") (pintype "bidirectional"))
      (node (ref "J4") (pin "TT") (pinfunction "38_TT") (pintype "bidirectional"))
      (node (ref "J4") (pin "UU") (pinfunction "39_UU") (pintype "bidirectional"))
      (node (ref "J4") (pin "VV") (pinfunction "40_VV") (pintype "bidirectional"))
      (node (ref "J5") (pin "5") (pinfunction "F_5") (pintype "passive"))
      (node (ref "R20") (pin "1") (pinfunction "1_1") (pintype "passive"))
      (node (ref "R7") (pin "1") (pinfunction "1_1") (pintype "passive"))
      (node (ref "S1") (pin "1") (pinfunction "1_1") (pintype "passive"))
      (node (ref "S1") (pin "2") (pinfunction "2_2") (pintype "passive"))
      (node (ref "S1") (pin "3") (pinfunction "3_3") (pintype "passive"))
      (node (ref "S1") (pin "4") (pinfunction "4_4") (pintype "passive"))
      (node (ref "S1") (pin "5") (pinfunction "5_5") (pintype "passive"))
      (node (ref "S1") (pin "6") (pinfunction "6_6") (pintype "passive"))
      (node (ref "S1") (pin "7") (pinfunction "7_7") (pintype "passive"))
      (node (ref "S1") (pin "8") (pinfunction "8_8") (pintype "passive"))
      (node (ref "SW2") (pin "3") (pinfunction "P_3") (pintype "passive"))
      (node (ref "SW2") (pin "4") (pinfunction "P1_4") (pintype "passive"))
      (node (ref "SW3") (pin "1") (pinfunction "1_1") (pintype "passive"))
      (node (ref "SW3") (pin "2") (pinfunction "1_2") (pintype "passive"))
      (node (ref "SW3") (pin "3") (pinfunction "1_3") (pintype "passive"))
      (node (ref "SW3") (pin "4") (pinfunction "1_4") (pintype "passive"))
      (node (ref "U1") (pin "22") (pinfunction "GND_22") (pintype "power_in"))
      (node (ref "U1") (pin "8") (pinfunction "GND_8") (pintype "power_in"))
      (node (ref "U11") (pin "1") (pinfunction "A0_1") (pintype "input"))
      (node (ref "U11") (pin "2") (pinfunction "A1_2") (pintype "input"))
      (node (ref "U11") (pin "3") (pinfunction "A2_3") (pintype "input"))
      (node (ref "U11") (pin "4") (pinfunction "GND_4") (pintype "power_in"))
      (node (ref "U11") (pin "7") (pinfunction "WP_7") (pintype "input"))
      (node (ref "U2") (pin "10") (pinfunction "VSS_10") (pintype "power_in"))
      (node (ref "U2") (pin "15") (pinfunction "A0_15") (pintype "input"))
      (node (ref "U2") (pin "16") (pinfunction "A1_16") (pintype "input"))
      (node (ref "U2") (pin "17") (pinfunction "A2_17") (pintype "input"))
    )
    (net (code "14") (name "INHIBIT") (class "Default")
      (node (ref "J1") (pin "AP2") (pinfunction "1_AP2") (pintype "bidirectional"))
    )
    (net (code "15") (name "INITIALIZE") (class "Default")
      (node (ref "J1") (pin "CR1") (pinfunction "1_CR1") (pintype "bidirectional"))
      (node (ref "Q1") (pin "1") (pinfunction "E_1") (pintype "passive"))
      (node (ref "U9") (pin "10") (pinfunction "I1_10") (pintype "input"))
      (node (ref "U9") (pin "9") (pinfunction "I0_9") (pintype "input"))
    )
    (net (code "16") (name "INT_IN_PROG") (class "Default")
      (node (ref "J1") (pin "BP2") (pinfunction "1_BP2") (pintype "bidirectional"))
    )
    (net (code "17") (name "INT_STROBE") (class "Default")
      (node (ref "J1") (pin "BD2") (pinfunction "1_BD2") (pintype "bidirectional"))
    )
    (net (code "18") (name "MEM00") (class "Default")
      (node (ref "E2") (pin "11") (pinfunction "I/O0_11") (pintype "tri_state"))
      (node (ref "E3") (pin "3") (pinfunction "O_3") (pintype "open_collector"))
      (node (ref "E3") (pin "4") (pinfunction "I0_4") (pintype "input"))
      (node (ref "RN1") (pin "8") (pinfunction "8_8") (pintype "passive"))
    )
    (net (code "19") (name "MEM01") (class "Default")
      (node (ref "E2") (pin "12") (pinfunction "I/O1_12") (pintype "tri_state"))
      (node (ref "E3") (pin "11") (pinfunction "O_11") (pintype "open_collector"))
      (node (ref "E3") (pin "9") (pinfunction "I0_9") (pintype "input"))
      (node (ref "RN1") (pin "6") (pinfunction "6_6") (pintype "passive"))
    )
    (net (code "20") (name "MEM02") (class "Default")
      (node (ref "E2") (pin "13") (pinfunction "I/O2_13") (pintype "tri_state"))
      (node (ref "E4") (pin "3") (pinfunction "O_3") (pintype "open_collector"))
      (node (ref "E4") (pin "4") (pinfunction "I0_4") (pintype "input"))
      (node (ref "RN1") (pin "4") (pinfunction "4_4") (pintype "passive"))
    )
    (net (code "21") (name "MEM03") (class "Default")
      (node (ref "E2") (pin "15") (pinfunction "I/O3_15") (pintype "tri_state"))
      (node (ref "E4") (pin "11") (pinfunction "O_11") (pintype "open_collector"))
      (node (ref "E4") (pin "9") (pinfunction "I0_9") (pintype "input"))
      (node (ref "RN1") (pin "2") (pinfunction "2_2") (pintype "passive"))
    )
    (net (code "22") (name "MEM04") (class "Default")
      (node (ref "E10") (pin "3") (pinfunction "O_3") (pintype "open_collector"))
      (node (ref "E10") (pin "4") (pinfunction "I0_4") (pintype "input"))
      (node (ref "E5") (pin "16") (pinfunction "I/O4_16") (pintype "tri_state"))
      (node (ref "RN2") (pin "3") (pinfunction "3_3") (pintype "passive"))
    )
    (net (code "23") (name "MEM05") (class "Default")
      (node (ref "E10") (pin "11") (pinfunction "O_11") (pintype "open_collector"))
      (node (ref "E10") (pin "9") (pinfunction "I0_9") (pintype "input"))
      (node (ref "E5") (pin "17") (pinfunction "I/O5_17") (pintype "tri_state"))
      (node (ref "RN2") (pin "4") (pinfunction "4_4") (pintype "passive"))
    )
    (net (code "24") (name "MEM06") (class "Default")
      (node (ref "E11") (pin "3") (pinfunction "O_3") (pintype "open_collector"))
      (node (ref "E11") (pin "4") (pinfunction "I0_4") (pintype "input"))
      (node (ref "E5") (pin "18") (pinfunction "I/O6_18") (pintype "tri_state"))
      (node (ref "RN2") (pin "6") (pinfunction "6_6") (pintype "passive"))
    )
    (net (code "25") (name "MEM07") (class "Default")
      (node (ref "E11") (pin "11") (pinfunction "O_11") (pintype "open_collector"))
      (node (ref "E11") (pin "9") (pinfunction "I0_9") (pintype "input"))
      (node (ref "E5") (pin "19") (pinfunction "I/O7_19") (pintype "tri_state"))
      (node (ref "RN2") (pin "8") (pinfunction "8_8") (pintype "passive"))
    )
    (net (code "26") (name "MEM08") (class "Default")
      (node (ref "E12") (pin "3") (pinfunction "O_3") (pintype "open_collector"))
      (node (ref "E12") (pin "4") (pinfunction "I0_4") (pintype "input"))
      (node (ref "E5") (pin "15") (pinfunction "I/O3_15") (pintype "tri_state"))
      (node (ref "RN2") (pin "2") (pinfunction "2_2") (pintype "passive"))
    )
    (net (code "27") (name "MEM09") (class "Default")
      (node (ref "E12") (pin "11") (pinfunction "O_11") (pintype "open_collector"))
      (node (ref "E12") (pin "9") (pinfunction "I0_9") (pintype "input"))
      (node (ref "E5") (pin "13") (pinfunction "I/O2_13") (pintype "tri_state"))
      (node (ref "RN2") (pin "5") (pinfunction "5_5") (pintype "passive"))
    )
    (net (code "28") (name "MEM10") (class "Default")
      (node (ref "E13") (pin "3") (pinfunction "O_3") (pintype "open_collector"))
      (node (ref "E13") (pin "4") (pinfunction "I0_4") (pintype "input"))
      (node (ref "E5") (pin "12") (pinfunction "I/O1_12") (pintype "tri_state"))
      (node (ref "RN2") (pin "7") (pinfunction "7_7") (pintype "passive"))
    )
    (net (code "29") (name "MEM11") (class "Default")
      (node (ref "E13") (pin "11") (pinfunction "O_11") (pintype "open_collector"))
      (node (ref "E13") (pin "9") (pinfunction "I0_9") (pintype "input"))
      (node (ref "E5") (pin "11") (pinfunction "I/O0_11") (pintype "tri_state"))
      (node (ref "RN2") (pin "9") (pinfunction "9_9") (pintype "passive"))
    )
    (net (code "30") (name "MEM12") (class "Default")
      (node (ref "E2") (pin "16") (pinfunction "I/O4_16") (pintype "tri_state"))
      (node (ref "RN1") (pin "3") (pinfunction "3_3") (pintype "passive"))
    )
    (net (code "31") (name "MEM13") (class "Default")
      (node (ref "E2") (pin "17") (pinfunction "I/O5_17") (pintype "tri_state"))
      (node (ref "RN1") (pin "5") (pinfunction "5_5") (pintype "passive"))
    )
    (net (code "32") (name "MEM14") (class "Default")
      (node (ref "E2") (pin "18") (pinfunction "I/O6_18") (pintype "tri_state"))
      (node (ref "RN1") (pin "7") (pinfunction "7_7") (pintype "passive"))
    )
    (net (code "33") (name "MEM15") (class "Default")
      (node (ref "E2") (pin "19") (pinfunction "I/O7_19") (pintype "tri_state"))
      (node (ref "RN1") (pin "9") (pinfunction "9_9") (pintype "passive"))
    )
    (net (code "34") (name "Net-(B1-+-Pad+@1)") (class "Default")
      (node (ref "B1") (pin "+") (pinfunction "+_+") (pintype "passive"))
      (node (ref "B1") (pin "+@1") (pinfunction "+_+@1") (pintype "passive"))
      (node (ref "B1") (pin "+@2") (pinfunction "+_+@2") (pintype "passive"))
      (node (ref "B1") (pin "+@3") (pinfunction "+_+@3") (pintype "passive"))
      (node (ref "B1") (pin "+@4") (pinfunction "+_+@4") (pintype "passive"))
      (node (ref "D2") (pin "A") (pinfunction "A_A") (pintype "passive"))
    )
    (net (code "35") (name "Net-(E9A-D0)") (class "Default")
      (node (ref "E9") (pin "4") (pinfunction "D0_4") (pintype "input"))
      (node (ref "R23") (pin "1") (pinfunction "1_1") (pintype "passive"))
      (node (ref "S1") (pin "16") (pinfunction "16_16") (pintype "passive"))
    )
    (net (code "36") (name "Net-(E9A-D1)") (class "Default")
      (node (ref "E9") (pin "3") (pinfunction "D1_3") (pintype "input"))
      (node (ref "R23") (pin "2") (pinfunction "1_2") (pintype "passive"))
      (node (ref "S1") (pin "15") (pinfunction "15_15") (pintype "passive"))
    )
    (net (code "37") (name "Net-(E9A-D2)") (class "Default")
      (node (ref "E9") (pin "2") (pinfunction "D2_2") (pintype "input"))
      (node (ref "R23") (pin "3") (pinfunction "1_3") (pintype "passive"))
      (node (ref "S1") (pin "14") (pinfunction "14_14") (pintype "passive"))
    )
    (net (code "38") (name "Net-(E9A-D3)") (class "Default")
      (node (ref "E9") (pin "1") (pinfunction "D3_1") (pintype "input"))
      (node (ref "R23") (pin "4") (pinfunction "1_4") (pintype "passive"))
      (node (ref "S1") (pin "13") (pinfunction "13_13") (pintype "passive"))
    )
    (net (code "39") (name "Net-(E9A-D4)") (class "Default")
      (node (ref "E9") (pin "15") (pinfunction "D4_15") (pintype "input"))
      (node (ref "R23") (pin "5") (pinfunction "1_5") (pintype "passive"))
      (node (ref "S1") (pin "12") (pinfunction "12_12") (pintype "passive"))
    )
    (net (code "40") (name "Net-(E9A-D5)") (class "Default")
      (node (ref "E9") (pin "14") (pinfunction "D5_14") (pintype "input"))
      (node (ref "R23") (pin "6") (pinfunction "1_6") (pintype "passive"))
      (node (ref "S1") (pin "11") (pinfunction "11_11") (pintype "passive"))
    )
    (net (code "41") (name "Net-(E9A-D6)") (class "Default")
      (node (ref "E9") (pin "13") (pinfunction "D6_13") (pintype "input"))
      (node (ref "R23") (pin "7") (pinfunction "1_7") (pintype "passive"))
      (node (ref "S1") (pin "10") (pinfunction "10_10") (pintype "passive"))
    )
    (net (code "42") (name "Net-(E9A-D7)") (class "Default")
      (node (ref "E9") (pin "12") (pinfunction "D7_12") (pintype "input"))
      (node (ref "R23") (pin "8") (pinfunction "1_8") (pintype "passive"))
      (node (ref "S1") (pin "9") (pinfunction "9_9") (pintype "passive"))
    )
    (net (code "43") (name "Net-(Q1-B)") (class "Default")
      (node (ref "Q1") (pin "2") (pinfunction "B_2") (pintype "passive"))
      (node (ref "R10") (pin "2") (pinfunction "2_2") (pintype "passive"))
    )
    (net (code "44") (name "Net-(Q1-C)") (class "Default")
      (node (ref "Q1") (pin "3") (pinfunction "C_3") (pintype "passive"))
      (node (ref "R5") (pin "1") (pinfunction "1_1") (pintype "passive"))
    )
    (net (code "45") (name "Net-(Q2-B)") (class "Default")
      (node (ref "Q2") (pin "2") (pinfunction "B_2") (pintype "passive"))
      (node (ref "R11") (pin "2") (pinfunction "2_2") (pintype "passive"))
    )
    (net (code "46") (name "Net-(Q2-C)") (class "Default")
      (node (ref "Q2") (pin "3") (pinfunction "C_3") (pintype "passive"))
      (node (ref "R6") (pin "1") (pinfunction "1_1") (pintype "passive"))
    )
    (net (code "47") (name "Net-(Q3-B)") (class "Default")
      (node (ref "Q3") (pin "2") (pinfunction "B_2") (pintype "passive"))
      (node (ref "R24") (pin "2") (pinfunction "2_2") (pintype "passive"))
    )
    (net (code "48") (name "Net-(SW2-S)") (class "Default")
      (node (ref "R12") (pin "2") (pinfunction "2_2") (pintype "passive"))
      (node (ref "SW2") (pin "1") (pinfunction "S_1") (pintype "passive"))
      (node (ref "SW2") (pin "2") (pinfunction "S1_2") (pintype "passive"))
    )
    (net (code "49") (name "Net-(SW3A-2)") (class "Default")
      (node (ref "R9") (pin "2") (pinfunction "2_2") (pintype "passive"))
      (node (ref "SW3") (pin "8") (pinfunction "2_8") (pintype "passive"))
    )
    (net (code "50") (name "Net-(SW3B-2)") (class "Default")
      (node (ref "R8") (pin "2") (pinfunction "2_2") (pintype "passive"))
      (node (ref "SW3") (pin "7") (pinfunction "2_7") (pintype "passive"))
    )
    (net (code "51") (name "Net-(SW3C-2)") (class "Default")
      (node (ref "R4") (pin "2") (pinfunction "2_2") (pintype "passive"))
      (node (ref "SW3") (pin "6") (pinfunction "2_6") (pintype "passive"))
    )
    (net (code "52") (name "Net-(SW3D-2)") (class "Default")
      (node (ref "R3") (pin "2") (pinfunction "2_2") (pintype "passive"))
      (node (ref "SW3") (pin "5") (pinfunction "2_5") (pintype "passive"))
    )
    (net (code "53") (name "Net-(U1-PB6(XTAL1{slash}TOSC1))") (class "Default")
      (node (ref "C9") (pin "1") (pinfunction "1_1") (pintype "passive"))
      (node (ref "R18") (pin "1") (pinfunction "1_1") (pintype "passive"))
      (node (ref "U1") (pin "9") (pinfunction "PB6(XTAL1/TOSC1)_9") (pintype "bidirectional"))
      (node (ref "Y1") (pin "2") (pinfunction "2_2") (pintype "passive"))
    )
    (net (code "54") (name "Net-(U1-PB7(XTAL2{slash}TOSC2))") (class "Default")
      (node (ref "C7") (pin "1") (pinfunction "1_1") (pintype "passive"))
      (node (ref "R18") (pin "2") (pinfunction "2_2") (pintype "passive"))
      (node (ref "U1") (pin "10") (pinfunction "PB7(XTAL2/TOSC2)_10") (pintype "bidirectional"))
      (node (ref "Y1") (pin "1") (pinfunction "1_1") (pintype "passive"))
    )
    (net (code "55") (name "Net-(U1-PD0(RXD))") (class "Default")
      (node (ref "R16") (pin "1") (pinfunction "1_1") (pintype "passive"))
      (node (ref "U1") (pin "2") (pinfunction "PD0(RXD)_2") (pintype "bidirectional"))
    )
    (net (code "56") (name "Net-(U1-PD1(TXD))") (class "Default")
      (node (ref "R17") (pin "1") (pinfunction "1_1") (pintype "passive"))
      (node (ref "U1") (pin "3") (pinfunction "PD1(TXD)_3") (pintype "bidirectional"))
    )
    (net (code "57") (name "Net-(U8A-O)") (class "Default")
      (node (ref "U8") (pin "12") (pinfunction "O_12") (pintype "output"))
      (node (ref "U8") (pin "3") (pinfunction "I0_3") (pintype "input"))
      (node (ref "U8") (pin "4") (pinfunction "I1_4") (pintype "input"))
      (node (ref "U8") (pin "5") (pinfunction "I2_5") (pintype "input"))
    )
    (net (code "58") (name "Net-(U8C-I0)") (class "Default")
      (node (ref "U8") (pin "9") (pinfunction "I0_9") (pintype "input"))
      (node (ref "U9") (pin "8") (pinfunction "O_8") (pintype "output"))
    )
    (net (code "59") (name "Net-(U8C-I1)") (class "Default")
      (node (ref "U8") (pin "10") (pinfunction "I1_10") (pintype "input"))
      (node (ref "U9") (pin "6") (pinfunction "O_6") (pintype "output"))
    )
    (net (code "60") (name "Net-(U8C-O)") (class "Default")
      (node (ref "U8") (pin "8") (pinfunction "O_8") (pintype "output"))
      (node (ref "U9") (pin "13") (pinfunction "I1_13") (pintype "input"))
      (node (ref "U9") (pin "2") (pinfunction "I1_2") (pintype "input"))
    )
    (net (code "61") (name "Net-(U9A-O)") (class "Default")
      (node (ref "U9") (pin "12") (pinfunction "I0_12") (pintype "input"))
      (node (ref "U9") (pin "3") (pinfunction "O_3") (pintype "output"))
    )
    (net (code "62") (name "Net-(U10A-C1+)") (class "Default")
      (node (ref "C14") (pin "1") (pinfunction "1_1") (pintype "passive"))
      (node (ref "U10") (pin "1") (pinfunction "C1+_1") (pintype "bidirectional"))
    )
    (net (code "63") (name "Net-(U10A-C1-)") (class "Default")
      (node (ref "C14") (pin "2") (pinfunction "2_2") (pintype "passive"))
      (node (ref "U10") (pin "3") (pinfunction "C1-_3") (pintype "bidirectional"))
    )
    (net (code "64") (name "Net-(U10A-C2+)") (class "Default")
      (node (ref "C15") (pin "1") (pinfunction "1_1") (pintype "passive"))
      (node (ref "U10") (pin "4") (pinfunction "C2+_4") (pintype "bidirectional"))
    )
    (net (code "65") (name "Net-(U10A-C2-)") (class "Default")
      (node (ref "C15") (pin "2") (pinfunction "2_2") (pintype "passive"))
      (node (ref "U10") (pin "5") (pinfunction "C2-_5") (pintype "bidirectional"))
    )
    (net (code "66") (name "Net-(U10A-V+)") (class "Default")
      (node (ref "C16") (pin "1") (pinfunction "1_1") (pintype "passive"))
      (node (ref "U10") (pin "2") (pinfunction "V+_2") (pintype "bidirectional"))
    )
    (net (code "67") (name "Net-(U10A-V-)") (class "Default")
      (node (ref "C17") (pin "2") (pinfunction "2_2") (pintype "passive"))
      (node (ref "U10") (pin "6") (pinfunction "V-_6") (pintype "bidirectional"))
    )
    (net (code "68") (name "OE") (class "Default")
      (node (ref "E10") (pin "10") (pinfunction "I1_10") (pintype "input"))
      (node (ref "E10") (pin "5") (pinfunction "I1_5") (pintype "input"))
      (node (ref "E11") (pin "10") (pinfunction "I1_10") (pintype "input"))
      (node (ref "E11") (pin "5") (pinfunction "I1_5") (pintype "input"))
      (node (ref "E12") (pin "10") (pinfunction "I1_10") (pintype "input"))
      (node (ref "E12") (pin "5") (pinfunction "I1_5") (pintype "input"))
      (node (ref "E13") (pin "10") (pinfunction "I1_10") (pintype "input"))
      (node (ref "E13") (pin "5") (pinfunction "I1_5") (pintype "input"))
      (node (ref "E3") (pin "10") (pinfunction "I1_10") (pintype "input"))
      (node (ref "E3") (pin "5") (pinfunction "I1_5") (pintype "input"))
      (node (ref "E4") (pin "10") (pinfunction "I1_10") (pintype "input"))
      (node (ref "E4") (pin "5") (pinfunction "I1_5") (pintype "input"))
      (node (ref "E6") (pin "12") (pinfunction "Y7_12") (pintype "tri_state"))
    )
    (net (code "69") (name "POWER_OK") (class "Default")
      (node (ref "J1") (pin "BV2") (pinfunction "1_BV2") (pintype "bidirectional"))
      (node (ref "R24") (pin "1") (pinfunction "1_1") (pintype "passive"))
    )
    (net (code "70") (name "PROG") (class "Default")
      (node (ref "C11") (pin "2") (pinfunction "2_2") (pintype "passive"))
      (node (ref "J2") (pin "1") (pinfunction "1_1") (pintype "passive"))
      (node (ref "R20") (pin "2") (pinfunction "2_2") (pintype "passive"))
      (node (ref "U10") (pin "11") (pinfunction "T1IN_11") (pintype "input"))
      (node (ref "U10") (pin "12") (pinfunction "R1OUT_12") (pintype "output"))
    )
    (net (code "71") (name "PULSE_LA") (class "Default")
      (node (ref "J1") (pin "DR2") (pinfunction "1_DR2") (pintype "bidirectional"))
      (node (ref "Q2") (pin "1") (pinfunction "E_1") (pintype "passive"))
    )
    (net (code "72") (name "RETURN") (class "Default")
      (node (ref "J1") (pin "AR2") (pinfunction "1_AR2") (pintype "bidirectional"))
    )
    (net (code "73") (name "ROM_ADDR") (class "Default")
      (node (ref "E6") (pin "11") (pinfunction "Y8_11") (pintype "tri_state"))
      (node (ref "E9") (pin "7") (pinfunction "G_7") (pintype "input"))
    )
    (net (code "74") (name "RXD") (class "Default")
      (node (ref "J2") (pin "2") (pinfunction "2_2") (pintype "passive"))
      (node (ref "R16") (pin "2") (pinfunction "2_2") (pintype "passive"))
      (node (ref "U10") (pin "9") (pinfunction "R2OUT_9") (pintype "output"))
    )
    (net (code "75") (name "RXD232") (class "Default")
      (node (ref "J4") (pin "J") (pinfunction "8_J") (pintype "bidirectional"))
      (node (ref "J5") (pin "2") (pinfunction "F_2") (pintype "passive"))
      (node (ref "U10") (pin "8") (pinfunction "R2IN_8") (pintype "input"))
    )
    (net (code "76") (name "R_RUN") (class "Default")
      (node (ref "R2") (pin "1") (pinfunction "1_1") (pintype "passive"))
      (node (ref "U1") (pin "14") (pinfunction "PB0(ICP)_14") (pintype "bidirectional"))
    )
    (net (code "77") (name "R_SW") (class "Default")
      (node (ref "C10") (pin "1") (pinfunction "1_1") (pintype "passive"))
      (node (ref "R1") (pin "1") (pinfunction "1_1") (pintype "passive"))
      (node (ref "R12") (pin "1") (pinfunction "1_1") (pintype "passive"))
      (node (ref "U1") (pin "15") (pinfunction "PB1(OC1A)_15") (pintype "bidirectional"))
    )
    (net (code "78") (name "SCL") (class "Default")
      (node (ref "R22") (pin "1") (pinfunction "1_1") (pintype "passive"))
      (node (ref "U1") (pin "28") (pinfunction "PC5(ADC5/SCL)_28") (pintype "bidirectional"))
      (node (ref "U11") (pin "6") (pinfunction "SCL_6") (pintype "input"))
      (node (ref "U2") (pin "12") (pinfunction "SCL_12") (pintype "input"))
    )
    (net (code "79") (name "SDA") (class "Default")
      (node (ref "R21") (pin "1") (pinfunction "1_1") (pintype "passive"))
      (node (ref "U1") (pin "27") (pinfunction "PC4(ADC4/SDA)_27") (pintype "bidirectional"))
      (node (ref "U11") (pin "5") (pinfunction "SDA_5") (pintype "bidirectional"))
      (node (ref "U2") (pin "13") (pinfunction "SDA_13") (pintype "bidirectional"))
    )
    (net (code "80") (name "SET_FF") (class "Default")
      (node (ref "U1") (pin "4") (pinfunction "PD2(INT0)_4") (pintype "bidirectional"))
      (node (ref "U9") (pin "1") (pinfunction "I0_1") (pintype "input"))
    )
    (net (code "81") (name "SHOW_DATA") (class "Default")
      (node (ref "U1") (pin "5") (pinfunction "PD3(INT1)_5") (pintype "bidirectional"))
      (node (ref "U8") (pin "1") (pinfunction "I0_1") (pintype "input"))
    )
    (net (code "82") (name "SOURCE") (class "Default")
      (node (ref "E6") (pin "3") (pinfunction "A2_3") (pintype "input"))
      (node (ref "J1") (pin "AL2") (pinfunction "1_AL2") (pintype "bidirectional"))
    )
    (net (code "83") (name "STROBE") (class "Default")
      (node (ref "J1") (pin "AM2") (pinfunction "1_AM2") (pintype "bidirectional"))
    )
    (net (code "84") (name "SW") (class "Default")
      (node (ref "J1") (pin "DV2") (pinfunction "1_DV2") (pintype "bidirectional"))
      (node (ref "R1") (pin "2") (pinfunction "2_2") (pintype "passive"))
    )
    (net (code "85") (name "TP1") (class "Default")
      (node (ref "J1") (pin "CD2") (pinfunction "1_CD2") (pintype "bidirectional"))
    )
    (net (code "86") (name "TP2") (class "Default")
      (node (ref "J1") (pin "CE2") (pinfunction "1_CE2") (pintype "bidirectional"))
    )
    (net (code "87") (name "TP3") (class "Default")
      (node (ref "J1") (pin "CH2") (pinfunction "1_CH2") (pintype "bidirectional"))
    )
    (net (code "88") (name "TP4") (class "Default")
      (node (ref "E6") (pin "2") (pinfunction "A1_2") (pintype "input"))
      (node (ref "J1") (pin "CJ2") (pinfunction "1_CJ2") (pintype "bidirectional"))
      (node (ref "U9") (pin "4") (pinfunction "I0_4") (pintype "input"))
      (node (ref "U9") (pin "5") (pinfunction "I1_5") (pintype "input"))
    )
    (net (code "89") (name "TXD") (class "Default")
      (node (ref "J2") (pin "3") (pinfunction "3_3") (pintype "passive"))
      (node (ref "R17") (pin "2") (pinfunction "2_2") (pintype "passive"))
      (node (ref "U10") (pin "10") (pinfunction "T2IN_10") (pintype "input"))
    )
    (net (code "90") (name "TXD232") (class "Default")
      (node (ref "J4") (pin "F") (pinfunction "6_F") (pintype "bidirectional"))
      (node (ref "J5") (pin "3") (pinfunction "F_3") (pintype "passive"))
      (node (ref "U10") (pin "7") (pinfunction "T2OUT_7") (pintype "output"))
    )
    (net (code "91") (name "V+") (class "Default")
      (node (ref "C20") (pin "1") (pinfunction "1_1") (pintype "passive"))
      (node (ref "C21") (pin "1") (pinfunction "1_1") (pintype "passive"))
      (node (ref "D2") (pin "C") (pinfunction "C_C") (pintype "passive"))
      (node (ref "D3") (pin "C") (pinfunction "C_C") (pintype "passive"))
      (node (ref "E2") (pin "28") (pinfunction "VCC_28") (pintype "power_in"))
      (node (ref "E5") (pin "28") (pinfunction "VCC_28") (pintype "power_in"))
      (node (ref "R15") (pin "2") (pinfunction "2_2") (pintype "passive"))
    )
    (net (code "92") (name "VCC") (class "Default")
      (node (ref "C1") (pin "1") (pinfunction "1_1") (pintype "passive"))
      (node (ref "C12") (pin "1") (pinfunction "1_1") (pintype "passive"))
      (node (ref "C13") (pin "1") (pinfunction "1_1") (pintype "passive"))
      (node (ref "C16") (pin "2") (pinfunction "2_2") (pintype "passive"))
      (node (ref "C18") (pin "1") (pinfunction "1_1") (pintype "passive"))
      (node (ref "C19") (pin "1") (pinfunction "1_1") (pintype "passive"))
      (node (ref "C2") (pin "1") (pinfunction "1_1") (pintype "passive"))
      (node (ref "C23") (pin "1") (pinfunction "1_1") (pintype "passive"))
      (node (ref "C24") (pin "1") (pinfunction "1_1") (pintype "passive"))
      (node (ref "C25") (pin "1") (pinfunction "1_1") (pintype "passive"))
      (node (ref "C26") (pin "1") (pinfunction "1_1") (pintype "passive"))
      (node (ref "C27") (pin "1") (pinfunction "1_1") (pintype "passive"))
      (node (ref "C28") (pin "1") (pinfunction "1_1") (pintype "passive"))
      (node (ref "C29") (pin "1") (pinfunction "1_1") (pintype "passive"))
      (node (ref "C3") (pin "1") (pinfunction "1_1") (pintype "passive"))
      (node (ref "C30") (pin "+") (pinfunction "+_+") (pintype "passive"))
      (node (ref "C31") (pin "1") (pinfunction "1_1") (pintype "passive"))
      (node (ref "C32") (pin "1") (pinfunction "1_1") (pintype "passive"))
      (node (ref "C33") (pin "1") (pinfunction "1_1") (pintype "passive"))
      (node (ref "C34") (pin "+") (pinfunction "+_+") (pintype "passive"))
      (node (ref "C35") (pin "+") (pinfunction "+_+") (pintype "passive"))
      (node (ref "C36") (pin "1") (pinfunction "1_1") (pintype "passive"))
      (node (ref "C37") (pin "1") (pinfunction "1_1") (pintype "passive"))
      (node (ref "C4") (pin "1") (pinfunction "1_1") (pintype "passive"))
      (node (ref "C5") (pin "1") (pinfunction "1_1") (pintype "passive"))
      (node (ref "C6") (pin "1") (pinfunction "1_1") (pintype "passive"))
      (node (ref "C8") (pin "1") (pinfunction "1_1") (pintype "passive"))
      (node (ref "D1") (pin "C") (pinfunction "C_C") (pintype "passive"))
      (node (ref "D3") (pin "A") (pinfunction "A_A") (pintype "passive"))
      (node (ref "J1") (pin "AA2") (pinfunction "1_AA2") (pintype "bidirectional"))
      (node (ref "J1") (pin "BA2") (pinfunction "1_BA2") (pintype "bidirectional"))
      (node (ref "J1") (pin "CA2") (pinfunction "1_CA2") (pintype "bidirectional"))
      (node (ref "J3") (pin "2") (pinfunction "2_2") (pintype "passive"))
      (node (ref "R13") (pin "2") (pinfunction "2_2") (pintype "passive"))
      (node (ref "R14") (pin "2") (pinfunction "2_2") (pintype "passive"))
      (node (ref "R19") (pin "2") (pinfunction "2_2") (pintype "passive"))
      (node (ref "R21") (pin "2") (pinfunction "2_2") (pintype "passive"))
      (node (ref "R22") (pin "2") (pinfunction "2_2") (pintype "passive"))
      (node (ref "R23") (pin "10") (pinfunction "2_10") (pintype "passive"))
      (node (ref "R23") (pin "11") (pinfunction "2_11") (pintype "passive"))
      (node (ref "R23") (pin "12") (pinfunction "2_12") (pintype "passive"))
      (node (ref "R23") (pin "13") (pinfunction "2_13") (pintype "passive"))
      (node (ref "R23") (pin "14") (pinfunction "2_14") (pintype "passive"))
      (node (ref "R23") (pin "15") (pinfunction "2_15") (pintype "passive"))
      (node (ref "R23") (pin "16") (pinfunction "2_16") (pintype "passive"))
      (node (ref "R23") (pin "9") (pinfunction "2_9") (pintype "passive"))
      (node (ref "R5") (pin "2") (pinfunction "2_2") (pintype "passive"))
      (node (ref "R6") (pin "2") (pinfunction "2_2") (pintype "passive"))
      (node (ref "RN1") (pin "1") (pinfunction "1_1") (pintype "passive"))
      (node (ref "RN2") (pin "1") (pinfunction "1_1") (pintype "passive"))
      (node (ref "U1") (pin "20") (pinfunction "AVCC_20") (pintype "power_in"))
      (node (ref "U1") (pin "21") (pinfunction "AREF_21") (pintype "passive"))
      (node (ref "U1") (pin "7") (pinfunction "VCC_7") (pintype "power_in"))
      (node (ref "U11") (pin "8") (pinfunction "VCC_8") (pintype "power_in"))
      (node (ref "U2") (pin "18") (pinfunction "~{RESET}_18") (pintype "input"))
      (node (ref "U2") (pin "9") (pinfunction "VDD_9") (pintype "power_in"))
      (node (ref "U7") (pin "12") (pinfunction "I0_12") (pintype "input"))
      (node (ref "U7") (pin "13") (pinfunction "I1_13") (pintype "input"))
    )
    (net (code "93") (name "WE") (class "Default")
      (node (ref "E10") (pin "13") (pinfunction "I1_13") (pintype "input"))
      (node (ref "E10") (pin "2") (pinfunction "I1_2") (pintype "input"))
      (node (ref "E11") (pin "13") (pinfunction "I1_13") (pintype "input"))
      (node (ref "E11") (pin "2") (pinfunction "I1_2") (pintype "input"))
      (node (ref "E12") (pin "13") (pinfunction "I1_13") (pintype "input"))
      (node (ref "E12") (pin "2") (pinfunction "I1_2") (pintype "input"))
      (node (ref "E13") (pin "13") (pinfunction "I1_13") (pintype "input"))
      (node (ref "E13") (pin "2") (pinfunction "I1_2") (pintype "input"))
      (node (ref "E3") (pin "13") (pinfunction "I1_13") (pintype "input"))
      (node (ref "E3") (pin "2") (pinfunction "I1_2") (pintype "input"))
      (node (ref "E4") (pin "13") (pinfunction "I1_13") (pintype "input"))
      (node (ref "E4") (pin "2") (pinfunction "I1_2") (pintype "input"))
      (node (ref "E6") (pin "13") (pinfunction "Y6_13") (pintype "tri_state"))
    )
    (net (code "94") (name "WRITE") (class "Default")
      (node (ref "E8") (pin "3") (pinfunction "I0_3") (pintype "input"))
      (node (ref "J1") (pin "AS2") (pinfunction "1_AS2") (pintype "bidirectional"))
    )
    (net (code "95") (name "W_DATA_00") (class "Default")
      (node (ref "U2") (pin "7") (pinfunction "GPB6_7") (pintype "bidirectional"))
      (node (ref "U3") (pin "2") (pinfunction "I1_2") (pintype "input"))
    )
    (net (code "96") (name "W_DATA_01") (class "Default")
      (node (ref "U2") (pin "6") (pinfunction "GPB5_6") (pintype "bidirectional"))
      (node (ref "U3") (pin "4") (pinfunction "I0_4") (pintype "input"))
    )
    (net (code "97") (name "W_DATA_02") (class "Default")
      (node (ref "U2") (pin "5") (pinfunction "GPB4_5") (pintype "bidirectional"))
      (node (ref "U3") (pin "12") (pinfunction "I0_12") (pintype "input"))
    )
    (net (code "98") (name "W_DATA_03") (class "Default")
      (node (ref "U2") (pin "3") (pinfunction "GPB2_3") (pintype "bidirectional"))
      (node (ref "U3") (pin "9") (pinfunction "I0_9") (pintype "input"))
    )
    (net (code "99") (name "W_DATA_04") (class "Default")
      (node (ref "U2") (pin "2") (pinfunction "GPB1_2") (pintype "bidirectional"))
      (node (ref "U4") (pin "2") (pinfunction "I1_2") (pintype "input"))
    )
    (net (code "100") (name "W_DATA_05") (class "Default")
      (node (ref "U2") (pin "1") (pinfunction "GPB0_1") (pintype "bidirectional"))
      (node (ref "U4") (pin "4") (pinfunction "I0_4") (pintype "input"))
    )
    (net (code "101") (name "W_DATA_06") (class "Default")
      (node (ref "U2") (pin "27") (pinfunction "GPA6_27") (pintype "bidirectional"))
      (node (ref "U4") (pin "12") (pinfunction "I0_12") (pintype "input"))
    )
    (net (code "102") (name "W_DATA_07") (class "Default")
      (node (ref "U2") (pin "26") (pinfunction "GPA5_26") (pintype "bidirectional"))
      (node (ref "U4") (pin "9") (pinfunction "I0_9") (pintype "input"))
    )
    (net (code "103") (name "W_DATA_08") (class "Default")
      (node (ref "U2") (pin "25") (pinfunction "GPA4_25") (pintype "bidirectional"))
      (node (ref "U5") (pin "2") (pinfunction "I1_2") (pintype "input"))
    )
    (net (code "104") (name "W_DATA_09") (class "Default")
      (node (ref "U2") (pin "23") (pinfunction "GPA2_23") (pintype "bidirectional"))
      (node (ref "U5") (pin "4") (pinfunction "I0_4") (pintype "input"))
    )
    (net (code "105") (name "W_DATA_10") (class "Default")
      (node (ref "U2") (pin "22") (pinfunction "GPA1_22") (pintype "bidirectional"))
      (node (ref "U5") (pin "12") (pinfunction "I0_12") (pintype "input"))
    )
    (net (code "106") (name "W_DATA_11") (class "Default")
      (node (ref "U2") (pin "21") (pinfunction "GPA0_21") (pintype "bidirectional"))
      (node (ref "U5") (pin "9") (pinfunction "I0_9") (pintype "input"))
    )
    (net (code "107") (name "W_INITIALIZE") (class "Default")
      (node (ref "R10") (pin "1") (pinfunction "1_1") (pintype "passive"))
      (node (ref "R13") (pin "1") (pinfunction "1_1") (pintype "passive"))
      (node (ref "U1") (pin "23") (pinfunction "PC0(ADC0)_23") (pintype "bidirectional"))
    )
    (net (code "108") (name "W_PULSE_LA") (class "Default")
      (node (ref "R11") (pin "1") (pinfunction "1_1") (pintype "passive"))
      (node (ref "R14") (pin "1") (pinfunction "1_1") (pintype "passive"))
      (node (ref "U1") (pin "24") (pinfunction "PC1(ADC1)_24") (pintype "bidirectional"))
    )
    (net (code "109") (name "W_STOP") (class "Default")
      (node (ref "U1") (pin "26") (pinfunction "PC3(ADC3)_26") (pintype "bidirectional"))
      (node (ref "U7") (pin "10") (pinfunction "I1_10") (pintype "input"))
      (node (ref "U7") (pin "9") (pinfunction "I0_9") (pintype "input"))
    )
    (net (code "110") (name "unconnected-(E1A-Y4-Pad12)") (class "Default")
      (node (ref "E1") (pin "12") (pinfunction "Y4_12") (pintype "tri_state"))
    )
    (net (code "111") (name "unconnected-(E9A-W-Pad6)") (class "Default")
      (node (ref "E9") (pin "6") (pinfunction "W_6") (pintype "output"))
    )
    (net (code "112") (name "unconnected-(J1A-1-PadAA1)") (class "Default")
      (node (ref "J1") (pin "AA1") (pinfunction "1_AA1") (pintype "bidirectional"))
    )
    (net (code "113") (name "unconnected-(J1AK-1-PadBA1)") (class "Default")
      (node (ref "J1") (pin "BA1") (pinfunction "1_BA1") (pintype "bidirectional"))
    )
    (net (code "114") (name "unconnected-(J1AM-1-PadBB1)") (class "Default")
      (node (ref "J1") (pin "BB1") (pinfunction "1_BB1") (pintype "bidirectional"))
    )
    (net (code "115") (name "unconnected-(J1BN-1-PadBS2)") (class "Default")
      (node (ref "J1") (pin "BS2") (pinfunction "1_BS2") (pintype "bidirectional"))
    )
    (net (code "116") (name "unconnected-(J1BU-1-PadCA1)") (class "Default")
      (node (ref "J1") (pin "CA1") (pinfunction "1_CA1") (pintype "bidirectional"))
    )
    (net (code "117") (name "unconnected-(J1BW-1-PadCB1)") (class "Default")
      (node (ref "J1") (pin "CB1") (pinfunction "1_CB1") (pintype "bidirectional"))
    )
    (net (code "118") (name "unconnected-(J1C-1-PadAB1)") (class "Default")
      (node (ref "J1") (pin "AB1") (pinfunction "1_AB1") (pintype "bidirectional"))
    )
    (net (code "119") (name "unconnected-(J1DE-1-PadDA1)") (class "Default")
      (node (ref "J1") (pin "DA1") (pinfunction "1_DA1") (pintype "bidirectional"))
    )
    (net (code "120") (name "unconnected-(J1DG-1-PadDB1)") (class "Default")
      (node (ref "J1") (pin "DB1") (pinfunction "1_DB1") (pintype "bidirectional"))
    )
    (net (code "121") (name "unconnected-(J4-3-PadC)") (class "Default")
      (node (ref "J4") (pin "C") (pinfunction "3_C") (pintype "bidirectional"))
    )
    (net (code "122") (name "unconnected-(J4-4-PadD)") (class "Default")
      (node (ref "J4") (pin "D") (pinfunction "4_D") (pintype "bidirectional"))
    )
    (net (code "123") (name "unconnected-(J4-5-PadE)") (class "Default")
      (node (ref "J4") (pin "E") (pinfunction "5_E") (pintype "bidirectional"))
    )
    (net (code "124") (name "unconnected-(J4-7-PadH)") (class "Default")
      (node (ref "J4") (pin "H") (pinfunction "7_H") (pintype "bidirectional"))
    )
    (net (code "125") (name "unconnected-(J4-9-PadK)") (class "Default")
      (node (ref "J4") (pin "K") (pinfunction "9_K") (pintype "bidirectional"))
    )
    (net (code "126") (name "unconnected-(J4-10-PadL)") (class "Default")
      (node (ref "J4") (pin "L") (pinfunction "10_L") (pintype "bidirectional"))
    )
    (net (code "127") (name "unconnected-(J4-11-PadM)") (class "Default")
      (node (ref "J4") (pin "M") (pinfunction "11_M") (pintype "bidirectional"))
    )
    (net (code "128") (name "unconnected-(J4-12-PadN)") (class "Default")
      (node (ref "J4") (pin "N") (pinfunction "12_N") (pintype "bidirectional"))
    )
    (net (code "129") (name "unconnected-(J4-13-PadP)") (class "Default")
      (node (ref "J4") (pin "P") (pinfunction "13_P") (pintype "bidirectional"))
    )
    (net (code "130") (name "unconnected-(J4-14-PadR)") (class "Default")
      (node (ref "J4") (pin "R") (pinfunction "14_R") (pintype "bidirectional"))
    )
    (net (code "131") (name "unconnected-(J4-15-PadS)") (class "Default")
      (node (ref "J4") (pin "S") (pinfunction "15_S") (pintype "bidirectional"))
    )
    (net (code "132") (name "unconnected-(J4-16-PadT)") (class "Default")
      (node (ref "J4") (pin "T") (pinfunction "16_T") (pintype "bidirectional"))
    )
    (net (code "133") (name "unconnected-(J4-17-PadU)") (class "Default")
      (node (ref "J4") (pin "U") (pinfunction "17_U") (pintype "bidirectional"))
    )
    (net (code "134") (name "unconnected-(J4-18-PadV)") (class "Default")
      (node (ref "J4") (pin "V") (pinfunction "18_V") (pintype "bidirectional"))
    )
    (net (code "135") (name "unconnected-(J4-19-PadW)") (class "Default")
      (node (ref "J4") (pin "W") (pinfunction "19_W") (pintype "bidirectional"))
    )
    (net (code "136") (name "unconnected-(J4-20-PadX)") (class "Default")
      (node (ref "J4") (pin "X") (pinfunction "20_X") (pintype "bidirectional"))
    )
    (net (code "137") (name "unconnected-(J4-21-PadY)") (class "Default")
      (node (ref "J4") (pin "Y") (pinfunction "21_Y") (pintype "bidirectional"))
    )
    (net (code "138") (name "unconnected-(J4-23-PadAA)") (class "Default")
      (node (ref "J4") (pin "AA") (pinfunction "23_AA") (pintype "bidirectional"))
    )
    (net (code "139") (name "unconnected-(J4-24-PadBB)") (class "Default")
      (node (ref "J4") (pin "BB") (pinfunction "24_BB") (pintype "bidirectional"))
    )
    (net (code "140") (name "unconnected-(J4-25-PadCC)") (class "Default")
      (node (ref "J4") (pin "CC") (pinfunction "25_CC") (pintype "bidirectional"))
    )
    (net (code "141") (name "unconnected-(J4-26-PadDD)") (class "Default")
      (node (ref "J4") (pin "DD") (pinfunction "26_DD") (pintype "bidirectional"))
    )
    (net (code "142") (name "unconnected-(J4-27-PadEE)") (class "Default")
      (node (ref "J4") (pin "EE") (pinfunction "27_EE") (pintype "bidirectional"))
    )
    (net (code "143") (name "unconnected-(J4-28-PadFF)") (class "Default")
      (node (ref "J4") (pin "FF") (pinfunction "28_FF") (pintype "bidirectional"))
    )
    (net (code "144") (name "unconnected-(J4-29-PadHH)") (class "Default")
      (node (ref "J4") (pin "HH") (pinfunction "29_HH") (pintype "bidirectional"))
    )
    (net (code "145") (name "unconnected-(J4-30-PadJJ)") (class "Default")
      (node (ref "J4") (pin "JJ") (pinfunction "30_JJ") (pintype "bidirectional"))
    )
    (net (code "146") (name "unconnected-(J4-31-PadKK)") (class "Default")
      (node (ref "J4") (pin "KK") (pinfunction "31_KK") (pintype "bidirectional"))
    )
    (net (code "147") (name "unconnected-(J4-32-PadLL)") (class "Default")
      (node (ref "J4") (pin "LL") (pinfunction "32_LL") (pintype "bidirectional"))
    )
    (net (code "148") (name "unconnected-(J4-33-PadMM)") (class "Default")
      (node (ref "J4") (pin "MM") (pinfunction "33_MM") (pintype "bidirectional"))
    )
    (net (code "149") (name "unconnected-(J4-34-PadNN)") (class "Default")
      (node (ref "J4") (pin "NN") (pinfunction "34_NN") (pintype "bidirectional"))
    )
    (net (code "150") (name "unconnected-(J4-35-PadPP)") (class "Default")
      (node (ref "J4") (pin "PP") (pinfunction "35_PP") (pintype "bidirectional"))
    )
    (net (code "151") (name "unconnected-(J4-36-PadRR)") (class "Default")
      (node (ref "J4") (pin "RR") (pinfunction "36_RR") (pintype "bidirectional"))
    )
    (net (code "152") (name "unconnected-(U2-GPA3-Pad24)") (class "Default")
      (node (ref "U2") (pin "24") (pinfunction "GPA3_24") (pintype "bidirectional"))
    )
    (net (code "153") (name "unconnected-(U2-GPA7-Pad28)") (class "Default")
      (node (ref "U2") (pin "28") (pinfunction "GPA7_28") (pintype "bidirectional"))
    )
    (net (code "154") (name "unconnected-(U2-GPB3-Pad4)") (class "Default")
      (node (ref "U2") (pin "4") (pinfunction "GPB3_4") (pintype "bidirectional"))
    )
    (net (code "155") (name "unconnected-(U2-GPB7-Pad8)") (class "Default")
      (node (ref "U2") (pin "8") (pinfunction "GPB7_8") (pintype "bidirectional"))
    )
    (net (code "156") (name "unconnected-(U2-INTA-Pad20)") (class "Default")
      (node (ref "U2") (pin "20") (pinfunction "INTA_20") (pintype "output"))
    )
    (net (code "157") (name "unconnected-(U2-INTB-Pad19)") (class "Default")
      (node (ref "U2") (pin "19") (pinfunction "INTB_19") (pintype "output"))
    )
    (net (code "158") (name "unconnected-(U7D-O-Pad11)") (class "Default")
      (node (ref "U7") (pin "11") (pinfunction "O_11") (pintype "open_collector"))
    )
    (net (code "159") (name "unconnected-(U10A-T1OUT-Pad14)") (class "Default")
      (node (ref "U10") (pin "14") (pinfunction "T1OUT_14") (pintype "output"))
    )
    (net (code "160") (name "~{BEMA0}") (class "Default")
      (node (ref "E1") (pin "18") (pinfunction "Y1_18") (pintype "tri_state"))
      (node (ref "E2") (pin "26") (pinfunction "A13_26") (pintype "input"))
      (node (ref "E5") (pin "26") (pinfunction "A13_26") (pintype "input"))
      (node (ref "E9") (pin "9") (pinfunction "C_9") (pintype "input"))
    )
    (net (code "161") (name "~{BEMA1}") (class "Default")
      (node (ref "E1") (pin "16") (pinfunction "Y2_16") (pintype "tri_state"))
      (node (ref "E2") (pin "25") (pinfunction "A8_25") (pintype "input"))
      (node (ref "E5") (pin "25") (pinfunction "A8_25") (pintype "input"))
      (node (ref "E9") (pin "10") (pinfunction "B_10") (pintype "input"))
    )
    (net (code "162") (name "~{BEMA2}") (class "Default")
      (node (ref "E1") (pin "14") (pinfunction "Y3_14") (pintype "tri_state"))
      (node (ref "E2") (pin "24") (pinfunction "A9_24") (pintype "input"))
      (node (ref "E5") (pin "24") (pinfunction "A9_24") (pintype "input"))
      (node (ref "E9") (pin "11") (pinfunction "A_11") (pintype "input"))
    )
    (net (code "163") (name "~{BMA00}") (class "Default")
      (node (ref "E1") (pin "9") (pinfunction "Y1_9") (pintype "tri_state"))
      (node (ref "E2") (pin "1") (pinfunction "A14_1") (pintype "input"))
      (node (ref "E5") (pin "1") (pinfunction "A14_1") (pintype "input"))
    )
    (net (code "164") (name "~{BMA01}") (class "Default")
      (node (ref "E1") (pin "7") (pinfunction "Y2_7") (pintype "tri_state"))
      (node (ref "E2") (pin "2") (pinfunction "A12_2") (pintype "input"))
      (node (ref "E5") (pin "2") (pinfunction "A12_2") (pintype "input"))
    )
    (net (code "165") (name "~{BMA02}") (class "Default")
      (node (ref "E1") (pin "5") (pinfunction "Y3_5") (pintype "tri_state"))
      (node (ref "E2") (pin "3") (pinfunction "A7_3") (pintype "input"))
      (node (ref "E5") (pin "3") (pinfunction "A7_3") (pintype "input"))
    )
    (net (code "166") (name "~{BMA03}") (class "Default")
      (node (ref "E1") (pin "3") (pinfunction "Y4_3") (pintype "tri_state"))
      (node (ref "E2") (pin "4") (pinfunction "A6_4") (pintype "input"))
      (node (ref "E5") (pin "4") (pinfunction "A6_4") (pintype "input"))
    )
    (net (code "167") (name "~{BMA04}") (class "Default")
      (node (ref "E2") (pin "5") (pinfunction "A5_5") (pintype "input"))
      (node (ref "E5") (pin "5") (pinfunction "A5_5") (pintype "input"))
      (node (ref "E7") (pin "3") (pinfunction "Y4_3") (pintype "tri_state"))
    )
    (net (code "168") (name "~{BMA05}") (class "Default")
      (node (ref "E2") (pin "6") (pinfunction "A4_6") (pintype "input"))
      (node (ref "E5") (pin "6") (pinfunction "A4_6") (pintype "input"))
      (node (ref "E7") (pin "5") (pinfunction "Y3_5") (pintype "tri_state"))
    )
    (net (code "169") (name "~{BMA06}") (class "Default")
      (node (ref "E2") (pin "7") (pinfunction "A3_7") (pintype "input"))
      (node (ref "E5") (pin "7") (pinfunction "A3_7") (pintype "input"))
      (node (ref "E7") (pin "7") (pinfunction "Y2_7") (pintype "tri_state"))
    )
    (net (code "170") (name "~{BMA07}") (class "Default")
      (node (ref "E2") (pin "8") (pinfunction "A2_8") (pintype "input"))
      (node (ref "E5") (pin "8") (pinfunction "A2_8") (pintype "input"))
      (node (ref "E7") (pin "9") (pinfunction "Y1_9") (pintype "tri_state"))
    )
    (net (code "171") (name "~{BMA08}") (class "Default")
      (node (ref "E2") (pin "9") (pinfunction "A1_9") (pintype "input"))
      (node (ref "E5") (pin "9") (pinfunction "A1_9") (pintype "input"))
      (node (ref "E7") (pin "18") (pinfunction "Y1_18") (pintype "tri_state"))
    )
    (net (code "172") (name "~{BMA09}") (class "Default")
      (node (ref "E2") (pin "10") (pinfunction "A0_10") (pintype "input"))
      (node (ref "E5") (pin "10") (pinfunction "A0_10") (pintype "input"))
      (node (ref "E7") (pin "16") (pinfunction "Y2_16") (pintype "tri_state"))
    )
    (net (code "173") (name "~{BMA10}") (class "Default")
      (node (ref "E2") (pin "21") (pinfunction "A10_21") (pintype "input"))
      (node (ref "E5") (pin "21") (pinfunction "A10_21") (pintype "input"))
      (node (ref "E7") (pin "14") (pinfunction "Y3_14") (pintype "tri_state"))
    )
    (net (code "174") (name "~{BMA11}") (class "Default")
      (node (ref "E2") (pin "23") (pinfunction "A11_23") (pintype "input"))
      (node (ref "E5") (pin "23") (pinfunction "A11_23") (pintype "input"))
      (node (ref "E7") (pin "12") (pinfunction "Y4_12") (pintype "tri_state"))
    )
    (net (code "175") (name "~{BMD_DIR}") (class "Default")
      (node (ref "E6") (pin "14") (pinfunction "Y5_14") (pintype "tri_state"))
      (node (ref "E8") (pin "4") (pinfunction "I1_4") (pintype "input"))
    )
    (net (code "176") (name "~{BREAK_CYCLE}") (class "Default")
      (node (ref "J1") (pin "BL2") (pinfunction "1_BL2") (pintype "bidirectional"))
    )
    (net (code "177") (name "~{BRK_DATA}") (class "Default")
      (node (ref "J1") (pin "BK2") (pinfunction "1_BK2") (pintype "bidirectional"))
      (node (ref "U7") (pin "3") (pinfunction "O_3") (pintype "open_collector"))
    )
    (net (code "178") (name "~{BRK_IN_PROG}") (class "Default")
      (node (ref "J1") (pin "BE2") (pinfunction "1_BE2") (pintype "bidirectional"))
    )
    (net (code "179") (name "~{BSOURCE}") (class "Default")
      (node (ref "E6") (pin "17") (pinfunction "Y2_17") (pintype "tri_state"))
      (node (ref "E6") (pin "4") (pinfunction "A3_4") (pintype "input"))
    )
    (net (code "180") (name "~{BUS_STROBE}") (class "Default")
      (node (ref "J1") (pin "CK1") (pinfunction "1_CK1") (pintype "bidirectional"))
    )
    (net (code "181") (name "~{C0}") (class "Default")
      (node (ref "J1") (pin "CE1") (pinfunction "1_CE1") (pintype "bidirectional"))
    )
    (net (code "182") (name "~{C1}") (class "Default")
      (node (ref "J1") (pin "CH1") (pinfunction "1_CH1") (pintype "bidirectional"))
    )
    (net (code "183") (name "~{C2}") (class "Default")
      (node (ref "J1") (pin "CJ1") (pinfunction "1_CJ1") (pintype "bidirectional"))
    )
    (net (code "184") (name "~{CE_OK}") (class "Default")
      (node (ref "C22") (pin "2") (pinfunction "2_2") (pintype "passive"))
      (node (ref "E8") (pin "12") (pinfunction "O_12") (pintype "output"))
      (node (ref "Q3") (pin "3") (pinfunction "E_3") (pintype "passive"))
    )
    (net (code "185") (name "~{CE}") (class "Default")
      (node (ref "C22") (pin "1") (pinfunction "1_1") (pintype "passive"))
      (node (ref "E2") (pin "20") (pinfunction "~{CE}_20") (pintype "input"))
      (node (ref "E5") (pin "20") (pinfunction "~{CE}_20") (pintype "input"))
      (node (ref "Q3") (pin "1") (pinfunction "C_1") (pintype "passive"))
      (node (ref "R15") (pin "1") (pinfunction "1_1") (pintype "passive"))
    )
    (net (code "186") (name "~{CPMA_DISABLE}") (class "Default")
      (node (ref "J1") (pin "CU1") (pinfunction "1_CU1") (pintype "bidirectional"))
    )
    (net (code "187") (name "~{DATA00}") (class "Default")
      (node (ref "J1") (pin "AR1") (pinfunction "1_AR1") (pintype "bidirectional"))
      (node (ref "U3") (pin "3") (pinfunction "O_3") (pintype "open_collector"))
    )
    (net (code "188") (name "~{DATA01}") (class "Default")
      (node (ref "J1") (pin "AS1") (pinfunction "1_AS1") (pintype "bidirectional"))
      (node (ref "U3") (pin "6") (pinfunction "O_6") (pintype "open_collector"))
    )
    (net (code "189") (name "~{DATA02}") (class "Default")
      (node (ref "J1") (pin "AU1") (pinfunction "1_AU1") (pintype "bidirectional"))
      (node (ref "U3") (pin "11") (pinfunction "O_11") (pintype "open_collector"))
    )
    (net (code "190") (name "~{DATA03}") (class "Default")
      (node (ref "J1") (pin "AV1") (pinfunction "1_AV1") (pintype "bidirectional"))
      (node (ref "U3") (pin "8") (pinfunction "O_8") (pintype "open_collector"))
    )
    (net (code "191") (name "~{DATA04}") (class "Default")
      (node (ref "J1") (pin "BR1") (pinfunction "1_BR1") (pintype "bidirectional"))
      (node (ref "U4") (pin "3") (pinfunction "O_3") (pintype "open_collector"))
    )
    (net (code "192") (name "~{DATA05}") (class "Default")
      (node (ref "J1") (pin "BS1") (pinfunction "1_BS1") (pintype "bidirectional"))
      (node (ref "U4") (pin "6") (pinfunction "O_6") (pintype "open_collector"))
    )
    (net (code "193") (name "~{DATA06}") (class "Default")
      (node (ref "J1") (pin "BU1") (pinfunction "1_BU1") (pintype "bidirectional"))
      (node (ref "U4") (pin "11") (pinfunction "O_11") (pintype "open_collector"))
    )
    (net (code "194") (name "~{DATA07}") (class "Default")
      (node (ref "J1") (pin "BV1") (pinfunction "1_BV1") (pintype "bidirectional"))
      (node (ref "U4") (pin "8") (pinfunction "O_8") (pintype "open_collector"))
    )
    (net (code "195") (name "~{DATA08}") (class "Default")
      (node (ref "J1") (pin "DR1") (pinfunction "1_DR1") (pintype "bidirectional"))
      (node (ref "U5") (pin "3") (pinfunction "O_3") (pintype "open_collector"))
    )
    (net (code "196") (name "~{DATA09}") (class "Default")
      (node (ref "J1") (pin "DS1") (pinfunction "1_DS1") (pintype "bidirectional"))
      (node (ref "U5") (pin "6") (pinfunction "O_6") (pintype "open_collector"))
    )
    (net (code "197") (name "~{DATA10}") (class "Default")
      (node (ref "J1") (pin "DU1") (pinfunction "1_DU1") (pintype "bidirectional"))
      (node (ref "U5") (pin "11") (pinfunction "O_11") (pintype "open_collector"))
    )
    (net (code "198") (name "~{DATA11}") (class "Default")
      (node (ref "J1") (pin "DV1") (pinfunction "1_DV1") (pintype "bidirectional"))
      (node (ref "U5") (pin "8") (pinfunction "O_8") (pintype "open_collector"))
    )
    (net (code "199") (name "~{DISABLE}") (class "Default")
      (node (ref "E8") (pin "1") (pinfunction "I0_1") (pintype "input"))
      (node (ref "E8") (pin "10") (pinfunction "I1_10") (pintype "input"))
      (node (ref "E8") (pin "11") (pinfunction "I2_11") (pintype "input"))
      (node (ref "E8") (pin "2") (pinfunction "I1_2") (pintype "input"))
      (node (ref "E9") (pin "5") (pinfunction "Y_5") (pintype "output"))
    )
    (net (code "200") (name "~{D}") (class "Default")
      (node (ref "J1") (pin "DK2") (pinfunction "1_DK2") (pintype "bidirectional"))
    )
    (net (code "201") (name "~{EMA0}") (class "Default")
      (node (ref "E1") (pin "2") (pinfunction "A1_2") (pintype "input"))
      (node (ref "J1") (pin "AD2") (pinfunction "1_AD2") (pintype "bidirectional"))
    )
    (net (code "202") (name "~{EMA1}") (class "Default")
      (node (ref "E1") (pin "4") (pinfunction "A2_4") (pintype "input"))
      (node (ref "J1") (pin "AE2") (pinfunction "1_AE2") (pintype "bidirectional"))
    )
    (net (code "203") (name "~{EMA2}") (class "Default")
      (node (ref "E1") (pin "6") (pinfunction "A3_6") (pintype "input"))
      (node (ref "J1") (pin "AH2") (pinfunction "1_AH2") (pintype "bidirectional"))
    )
    (net (code "204") (name "~{E}") (class "Default")
      (node (ref "J1") (pin "DL2") (pinfunction "1_DL2") (pintype "bidirectional"))
    )
    (net (code "205") (name "~{FSET}") (class "Default")
      (node (ref "J1") (pin "DP2") (pinfunction "1_DP2") (pintype "bidirectional"))
    )
    (net (code "206") (name "~{F}") (class "Default")
      (node (ref "J1") (pin "DJ2") (pinfunction "1_DJ2") (pintype "bidirectional"))
    )
    (net (code "207") (name "~{IND1}") (class "Default")
      (node (ref "J1") (pin "CU2") (pinfunction "1_CU2") (pintype "bidirectional"))
    )
    (net (code "208") (name "~{IND2}") (class "Default")
      (node (ref "J1") (pin "CV2") (pinfunction "1_CV2") (pintype "bidirectional"))
    )
    (net (code "209") (name "~{INTERNAL_IO}") (class "Default")
      (node (ref "J1") (pin "CL1") (pinfunction "1_CL1") (pintype "bidirectional"))
    )
    (net (code "210") (name "~{INT_RQST}") (class "Default")
      (node (ref "J1") (pin "CP1") (pinfunction "1_CP1") (pintype "bidirectional"))
    )
    (net (code "211") (name "~{IO_PAUSE}") (class "Default")
      (node (ref "J1") (pin "CD1") (pinfunction "1_CD1") (pintype "bidirectional"))
    )
    (net (code "212") (name "~{IR0}") (class "Default")
      (node (ref "J1") (pin "DD2") (pinfunction "1_DD2") (pintype "bidirectional"))
    )
    (net (code "213") (name "~{IR1}") (class "Default")
      (node (ref "J1") (pin "DE2") (pinfunction "1_DE2") (pintype "bidirectional"))
    )
    (net (code "214") (name "~{IR2}") (class "Default")
      (node (ref "J1") (pin "DH2") (pinfunction "1_DH2") (pintype "bidirectional"))
    )
    (net (code "215") (name "~{KEY_CONT}") (class "Default")
      (node (ref "J1") (pin "DU2") (pinfunction "1_DU2") (pintype "bidirectional"))
      (node (ref "U6") (pin "11") (pinfunction "O_11") (pintype "open_collector"))
    )
    (net (code "216") (name "~{LA_ENABLE}") (class "Default")
      (node (ref "J1") (pin "BM2") (pinfunction "1_BM2") (pintype "bidirectional"))
      (node (ref "U6") (pin "6") (pinfunction "O_6") (pintype "open_collector"))
    )
    (net (code "217") (name "~{LINK_DATA}") (class "Default")
      (node (ref "J1") (pin "CR2") (pinfunction "1_CR2") (pintype "bidirectional"))
    )
    (net (code "218") (name "~{LINK_LOAD}") (class "Default")
      (node (ref "J1") (pin "CS2") (pinfunction "1_CS2") (pintype "bidirectional"))
    )
    (net (code "219") (name "~{LINK}") (class "Default")
      (node (ref "J1") (pin "AV2") (pinfunction "1_AV2") (pintype "bidirectional"))
    )
    (net (code "220") (name "~{LOAD_CONT}") (class "Default")
      (node (ref "J1") (pin "BH2") (pinfunction "1_BH2") (pintype "bidirectional"))
    )
    (net (code "221") (name "~{MA00}") (class "Default")
      (node (ref "E1") (pin "11") (pinfunction "A1_11") (pintype "input"))
      (node (ref "J1") (pin "AD1") (pinfunction "1_AD1") (pintype "bidirectional"))
    )
    (net (code "222") (name "~{MA01}") (class "Default")
      (node (ref "E1") (pin "13") (pinfunction "A2_13") (pintype "input"))
      (node (ref "J1") (pin "AE1") (pinfunction "1_AE1") (pintype "bidirectional"))
    )
    (net (code "223") (name "~{MA02}") (class "Default")
      (node (ref "E1") (pin "15") (pinfunction "A3_15") (pintype "input"))
      (node (ref "J1") (pin "AH1") (pinfunction "1_AH1") (pintype "bidirectional"))
    )
    (net (code "224") (name "~{MA03}") (class "Default")
      (node (ref "E1") (pin "17") (pinfunction "A4_17") (pintype "input"))
      (node (ref "J1") (pin "AJ1") (pinfunction "1_AJ1") (pintype "bidirectional"))
    )
    (net (code "225") (name "~{MA04}") (class "Default")
      (node (ref "E7") (pin "17") (pinfunction "A4_17") (pintype "input"))
      (node (ref "J1") (pin "BD1") (pinfunction "1_BD1") (pintype "bidirectional"))
    )
    (net (code "226") (name "~{MA05}") (class "Default")
      (node (ref "E7") (pin "15") (pinfunction "A3_15") (pintype "input"))
      (node (ref "J1") (pin "BE1") (pinfunction "1_BE1") (pintype "bidirectional"))
    )
    (net (code "227") (name "~{MA06}") (class "Default")
      (node (ref "E7") (pin "13") (pinfunction "A2_13") (pintype "input"))
      (node (ref "J1") (pin "BH1") (pinfunction "1_BH1") (pintype "bidirectional"))
    )
    (net (code "228") (name "~{MA07}") (class "Default")
      (node (ref "E7") (pin "11") (pinfunction "A1_11") (pintype "input"))
      (node (ref "J1") (pin "BJ1") (pinfunction "1_BJ1") (pintype "bidirectional"))
    )
    (net (code "229") (name "~{MA08}") (class "Default")
      (node (ref "E7") (pin "2") (pinfunction "A1_2") (pintype "input"))
      (node (ref "J1") (pin "DD1") (pinfunction "1_DD1") (pintype "bidirectional"))
    )
    (net (code "230") (name "~{MA09}") (class "Default")
      (node (ref "E7") (pin "4") (pinfunction "A2_4") (pintype "input"))
      (node (ref "J1") (pin "DE1") (pinfunction "1_DE1") (pintype "bidirectional"))
    )
    (net (code "231") (name "~{MA10}") (class "Default")
      (node (ref "E7") (pin "6") (pinfunction "A3_6") (pintype "input"))
      (node (ref "J1") (pin "DH1") (pinfunction "1_DH1") (pintype "bidirectional"))
    )
    (net (code "232") (name "~{MA11}") (class "Default")
      (node (ref "E7") (pin "8") (pinfunction "A4_8") (pintype "input"))
      (node (ref "J1") (pin "DJ1") (pinfunction "1_DJ1") (pintype "bidirectional"))
    )
    (net (code "233") (name "~{MD00}") (class "Default")
      (node (ref "E3") (pin "1") (pinfunction "I0_1") (pintype "input"))
      (node (ref "E3") (pin "6") (pinfunction "O_6") (pintype "open_collector"))
      (node (ref "J1") (pin "AK1") (pinfunction "1_AK1") (pintype "bidirectional"))
    )
    (net (code "234") (name "~{MD01}") (class "Default")
      (node (ref "E3") (pin "12") (pinfunction "I0_12") (pintype "input"))
      (node (ref "E3") (pin "8") (pinfunction "O_8") (pintype "open_collector"))
      (node (ref "J1") (pin "AL1") (pinfunction "1_AL1") (pintype "bidirectional"))
    )
    (net (code "235") (name "~{MD02}") (class "Default")
      (node (ref "E4") (pin "1") (pinfunction "I0_1") (pintype "input"))
      (node (ref "E4") (pin "6") (pinfunction "O_6") (pintype "open_collector"))
      (node (ref "J1") (pin "AM1") (pinfunction "1_AM1") (pintype "bidirectional"))
    )
    (net (code "236") (name "~{MD03}") (class "Default")
      (node (ref "E4") (pin "12") (pinfunction "I0_12") (pintype "input"))
      (node (ref "E4") (pin "8") (pinfunction "O_8") (pintype "open_collector"))
      (node (ref "J1") (pin "AP1") (pinfunction "1_AP1") (pintype "bidirectional"))
    )
    (net (code "237") (name "~{MD04}") (class "Default")
      (node (ref "E10") (pin "1") (pinfunction "I0_1") (pintype "input"))
      (node (ref "E10") (pin "6") (pinfunction "O_6") (pintype "open_collector"))
      (node (ref "J1") (pin "BK1") (pinfunction "1_BK1") (pintype "bidirectional"))
    )
    (net (code "238") (name "~{MD05}") (class "Default")
      (node (ref "E10") (pin "12") (pinfunction "I0_12") (pintype "input"))
      (node (ref "E10") (pin "8") (pinfunction "O_8") (pintype "open_collector"))
      (node (ref "J1") (pin "BL1") (pinfunction "1_BL1") (pintype "bidirectional"))
    )
    (net (code "239") (name "~{MD06}") (class "Default")
      (node (ref "E11") (pin "1") (pinfunction "I0_1") (pintype "input"))
      (node (ref "E11") (pin "6") (pinfunction "O_6") (pintype "open_collector"))
      (node (ref "J1") (pin "BM1") (pinfunction "1_BM1") (pintype "bidirectional"))
    )
    (net (code "240") (name "~{MD07}") (class "Default")
      (node (ref "E11") (pin "12") (pinfunction "I0_12") (pintype "input"))
      (node (ref "E11") (pin "8") (pinfunction "O_8") (pintype "open_collector"))
      (node (ref "J1") (pin "BP1") (pinfunction "1_BP1") (pintype "bidirectional"))
    )
    (net (code "241") (name "~{MD08}") (class "Default")
      (node (ref "E12") (pin "1") (pinfunction "I0_1") (pintype "input"))
      (node (ref "E12") (pin "6") (pinfunction "O_6") (pintype "open_collector"))
      (node (ref "J1") (pin "DK1") (pinfunction "1_DK1") (pintype "bidirectional"))
    )
    (net (code "242") (name "~{MD09}") (class "Default")
      (node (ref "E12") (pin "12") (pinfunction "I0_12") (pintype "input"))
      (node (ref "E12") (pin "8") (pinfunction "O_8") (pintype "open_collector"))
      (node (ref "J1") (pin "DL1") (pinfunction "1_DL1") (pintype "bidirectional"))
    )
    (net (code "243") (name "~{MD10}") (class "Default")
      (node (ref "E13") (pin "1") (pinfunction "I0_1") (pintype "input"))
      (node (ref "E13") (pin "6") (pinfunction "O_6") (pintype "open_collector"))
      (node (ref "J1") (pin "DM1") (pinfunction "1_DM1") (pintype "bidirectional"))
    )
    (net (code "244") (name "~{MD11}") (class "Default")
      (node (ref "E13") (pin "12") (pinfunction "I0_12") (pintype "input"))
      (node (ref "E13") (pin "8") (pinfunction "O_8") (pintype "open_collector"))
      (node (ref "J1") (pin "DP1") (pinfunction "1_DP1") (pintype "bidirectional"))
    )
    (net (code "245") (name "~{MD_DIR}") (class "Default")
      (node (ref "E6") (pin "5") (pinfunction "A4_5") (pintype "input"))
      (node (ref "J1") (pin "AK2") (pinfunction "1_AK2") (pintype "bidirectional"))
      (node (ref "U7") (pin "6") (pinfunction "O_6") (pintype "open_collector"))
    )
    (net (code "246") (name "~{MEM_START}") (class "Default")
      (node (ref "J1") (pin "AJ2") (pinfunction "1_AJ2") (pintype "bidirectional"))
      (node (ref "U6") (pin "3") (pinfunction "O_3") (pintype "open_collector"))
    )
    (net (code "247") (name "~{MS_DISABLE}") (class "Default")
      (node (ref "J1") (pin "CV1") (pinfunction "1_CV1") (pintype "bidirectional"))
      (node (ref "U6") (pin "8") (pinfunction "O_8") (pintype "open_collector"))
    )
    (net (code "248") (name "~{NOT_LAST_TR}") (class "Default")
      (node (ref "J1") (pin "CM1") (pinfunction "1_CM1") (pintype "bidirectional"))
    )
    (net (code "249") (name "~{NTS_STALL}") (class "Default")
      (node (ref "J1") (pin "BR2") (pinfunction "1_BR2") (pintype "bidirectional"))
    )
    (net (code "250") (name "~{OE}") (class "Default")
      (node (ref "E2") (pin "22") (pinfunction "~{OE}_22") (pintype "input"))
      (node (ref "E5") (pin "22") (pinfunction "~{OE}_22") (pintype "input"))
      (node (ref "E6") (pin "8") (pinfunction "A7_8") (pintype "input"))
      (node (ref "E8") (pin "8") (pinfunction "O_8") (pintype "output"))
    )
    (net (code "251") (name "~{OVERFLOW}") (class "Default")
      (node (ref "J1") (pin "BJ2") (pinfunction "1_BJ2") (pintype "bidirectional"))
    )
    (net (code "252") (name "~{RESET}") (class "Default")
      (node (ref "C11") (pin "1") (pinfunction "1_1") (pintype "passive"))
      (node (ref "D1") (pin "A") (pinfunction "A_A") (pintype "passive"))
      (node (ref "J3") (pin "5") (pinfunction "5_5") (pintype "passive"))
      (node (ref "R19") (pin "1") (pinfunction "1_1") (pintype "passive"))
      (node (ref "U1") (pin "1") (pinfunction "PC6(/RESET)_1") (pintype "bidirectional"))
    )
    (net (code "253") (name "~{ROM_ADDR}") (class "Default")
      (node (ref "E6") (pin "9") (pinfunction "A8_9") (pintype "input"))
      (node (ref "J1") (pin "AU2") (pinfunction "1_AU2") (pintype "bidirectional"))
    )
    (net (code "254") (name "~{RUN}") (class "Default")
      (node (ref "J1") (pin "BU2") (pinfunction "1_BU2") (pintype "bidirectional"))
      (node (ref "R2") (pin "2") (pinfunction "2_2") (pintype "passive"))
    )
    (net (code "255") (name "~{SKIP}") (class "Default")
      (node (ref "J1") (pin "CS1") (pinfunction "1_CS1") (pintype "bidirectional"))
    )
    (net (code "256") (name "~{STOP}") (class "Default")
      (node (ref "J1") (pin "DS2") (pinfunction "1_DS2") (pintype "bidirectional"))
      (node (ref "U7") (pin "8") (pinfunction "O_8") (pintype "open_collector"))
    )
    (net (code "257") (name "~{TP4}") (class "Default")
      (node (ref "E6") (pin "18") (pinfunction "Y1_18") (pintype "tri_state"))
      (node (ref "E8") (pin "13") (pinfunction "I2_13") (pintype "input"))
    )
    (net (code "258") (name "~{TS1}") (class "Default")
      (node (ref "J1") (pin "CK2") (pinfunction "1_CK2") (pintype "bidirectional"))
    )
    (net (code "259") (name "~{TS2}") (class "Default")
      (node (ref "J1") (pin "CL2") (pinfunction "1_CL2") (pintype "bidirectional"))
    )
    (net (code "260") (name "~{TS3}") (class "Default")
      (node (ref "J1") (pin "CM2") (pinfunction "1_CM2") (pintype "bidirectional"))
    )
    (net (code "261") (name "~{TS4}") (class "Default")
      (node (ref "J1") (pin "CP2") (pinfunction "1_CP2") (pintype "bidirectional"))
      (node (ref "U8") (pin "13") (pinfunction "I2_13") (pintype "input"))
    )
    (net (code "262") (name "~{USER_MODE}") (class "Default")
      (node (ref "J1") (pin "DM2") (pinfunction "1_DM2") (pintype "bidirectional"))
    )
    (net (code "263") (name "~{WE}") (class "Default")
      (node (ref "E2") (pin "27") (pinfunction "~{WE}_27") (pintype "input"))
      (node (ref "E5") (pin "27") (pinfunction "~{WE}_27") (pintype "input"))
      (node (ref "E6") (pin "7") (pinfunction "A6_7") (pintype "input"))
      (node (ref "E8") (pin "6") (pinfunction "O_6") (pintype "output"))
    )
    (net (code "264") (name "~{W_KEY_CONTROL}") (class "Default")
      (node (ref "U1") (pin "13") (pinfunction "PD7(AIN1)_13") (pintype "bidirectional"))
      (node (ref "U6") (pin "12") (pinfunction "I0_12") (pintype "input"))
    )
    (net (code "265") (name "~{W_LA_ENABLE}") (class "Default")
      (node (ref "U1") (pin "11") (pinfunction "PD5(T1)_11") (pintype "bidirectional"))
      (node (ref "U6") (pin "4") (pinfunction "I0_4") (pintype "input"))
    )
    (net (code "266") (name "~{W_MEM_START}") (class "Default")
      (node (ref "R7") (pin "2") (pinfunction "2_2") (pintype "passive"))
      (node (ref "U1") (pin "25") (pinfunction "PC2(ADC2)_25") (pintype "bidirectional"))
      (node (ref "U6") (pin "1") (pinfunction "I0_1") (pintype "input"))
      (node (ref "U6") (pin "2") (pinfunction "I1_2") (pintype "input"))
    )
    (net (code "267") (name "~{W_MS_IR_DISABLE}") (class "Default")
      (node (ref "U1") (pin "12") (pinfunction "PD6(AIN0)_12") (pintype "bidirectional"))
      (node (ref "U6") (pin "9") (pinfunction "I0_9") (pintype "input"))
    )
  )
)
